# interfacez_main_r2_4.net
KiCad netlist of a schematic drawn in EAGLE
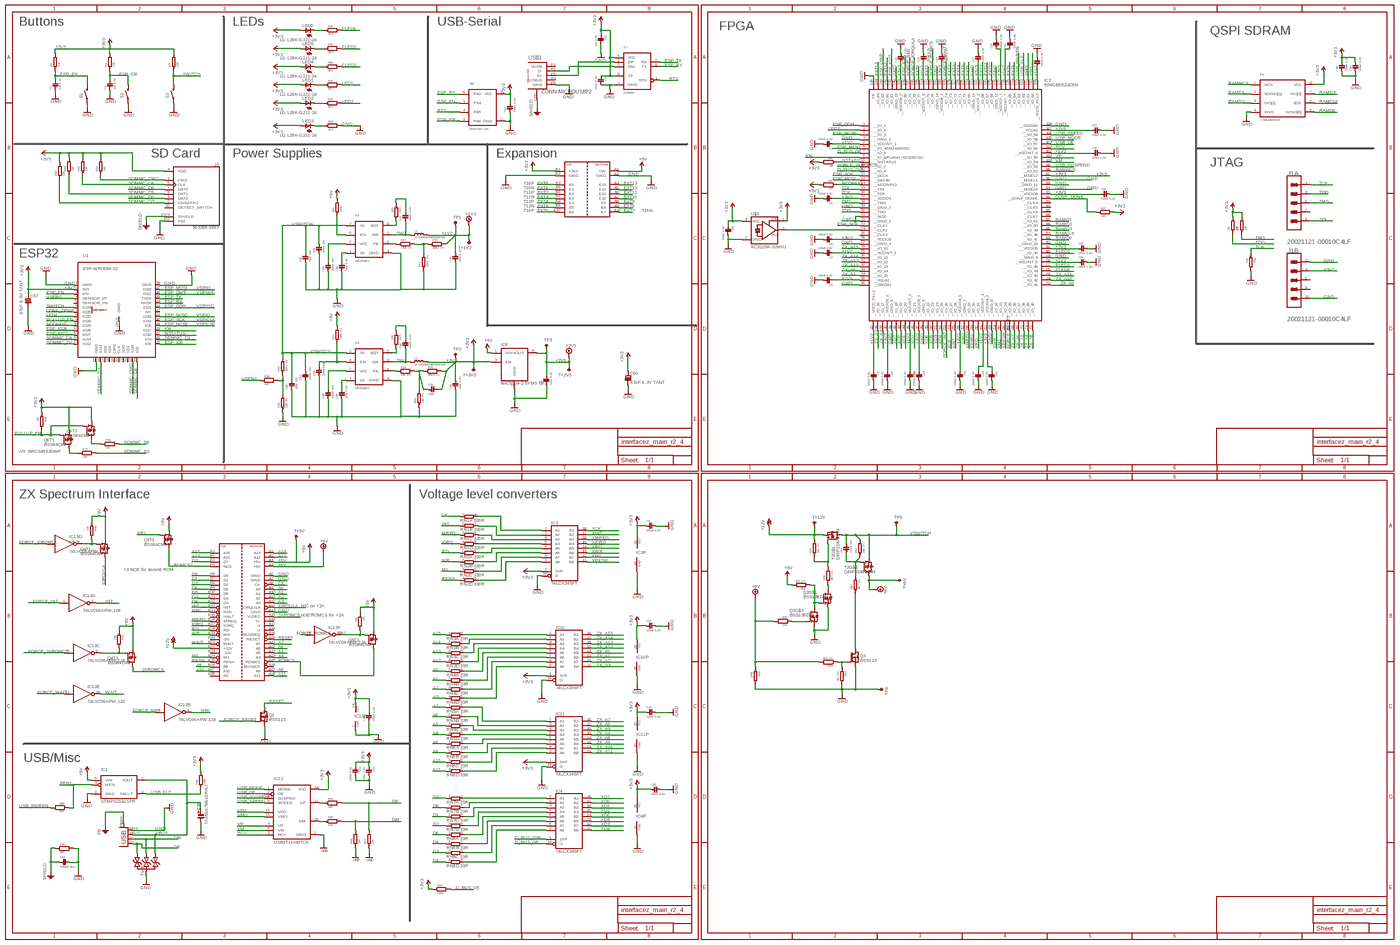
[diagram p0: schematic, sheet 1, overview]
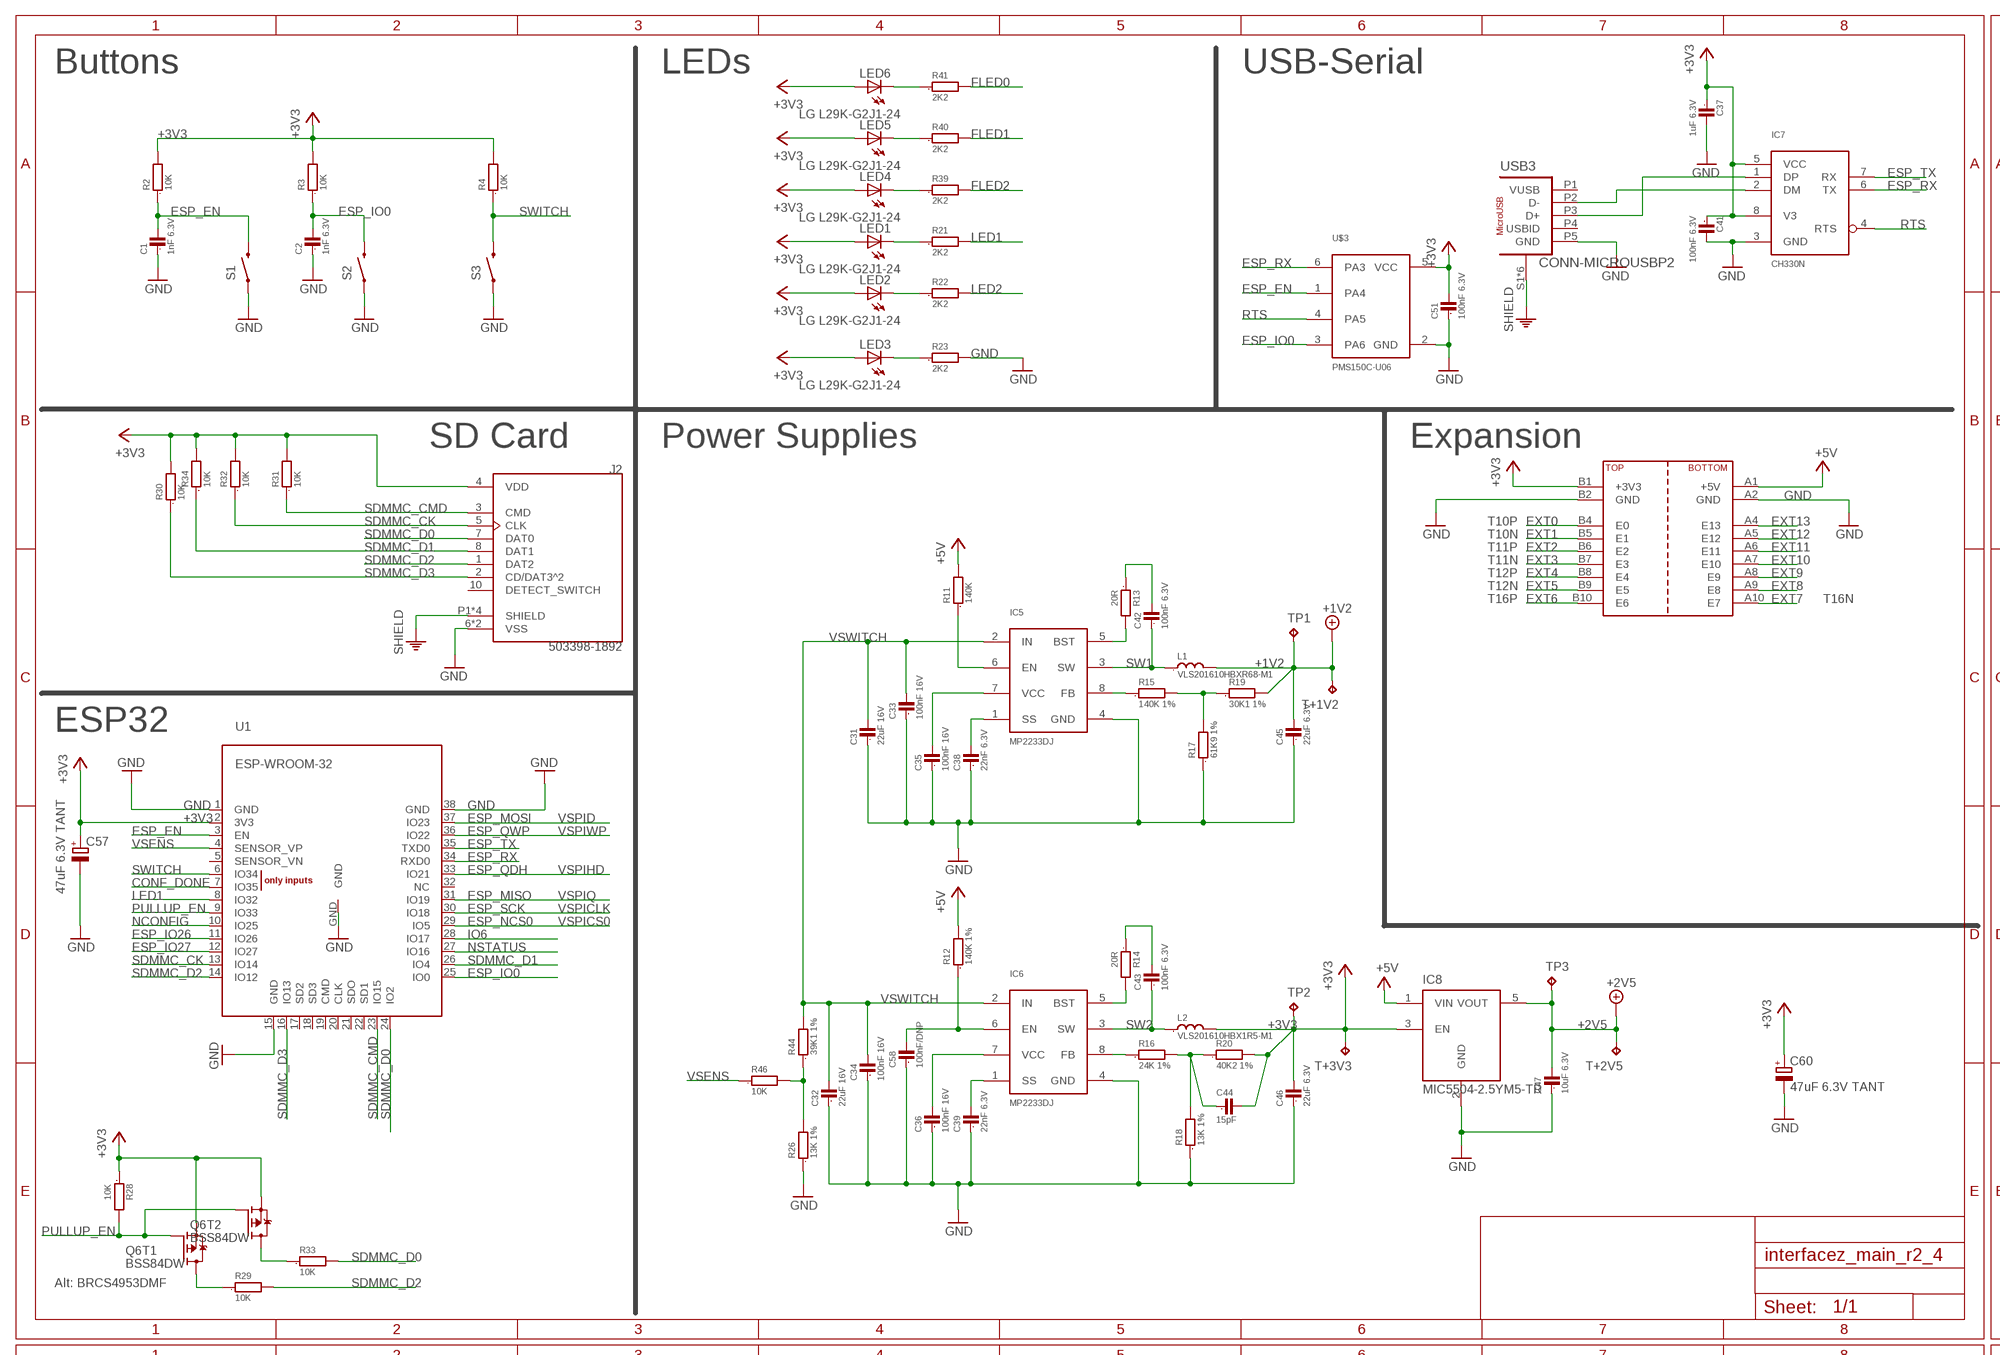
[diagram p1: schematic, sheet 1, part 1 of 4]
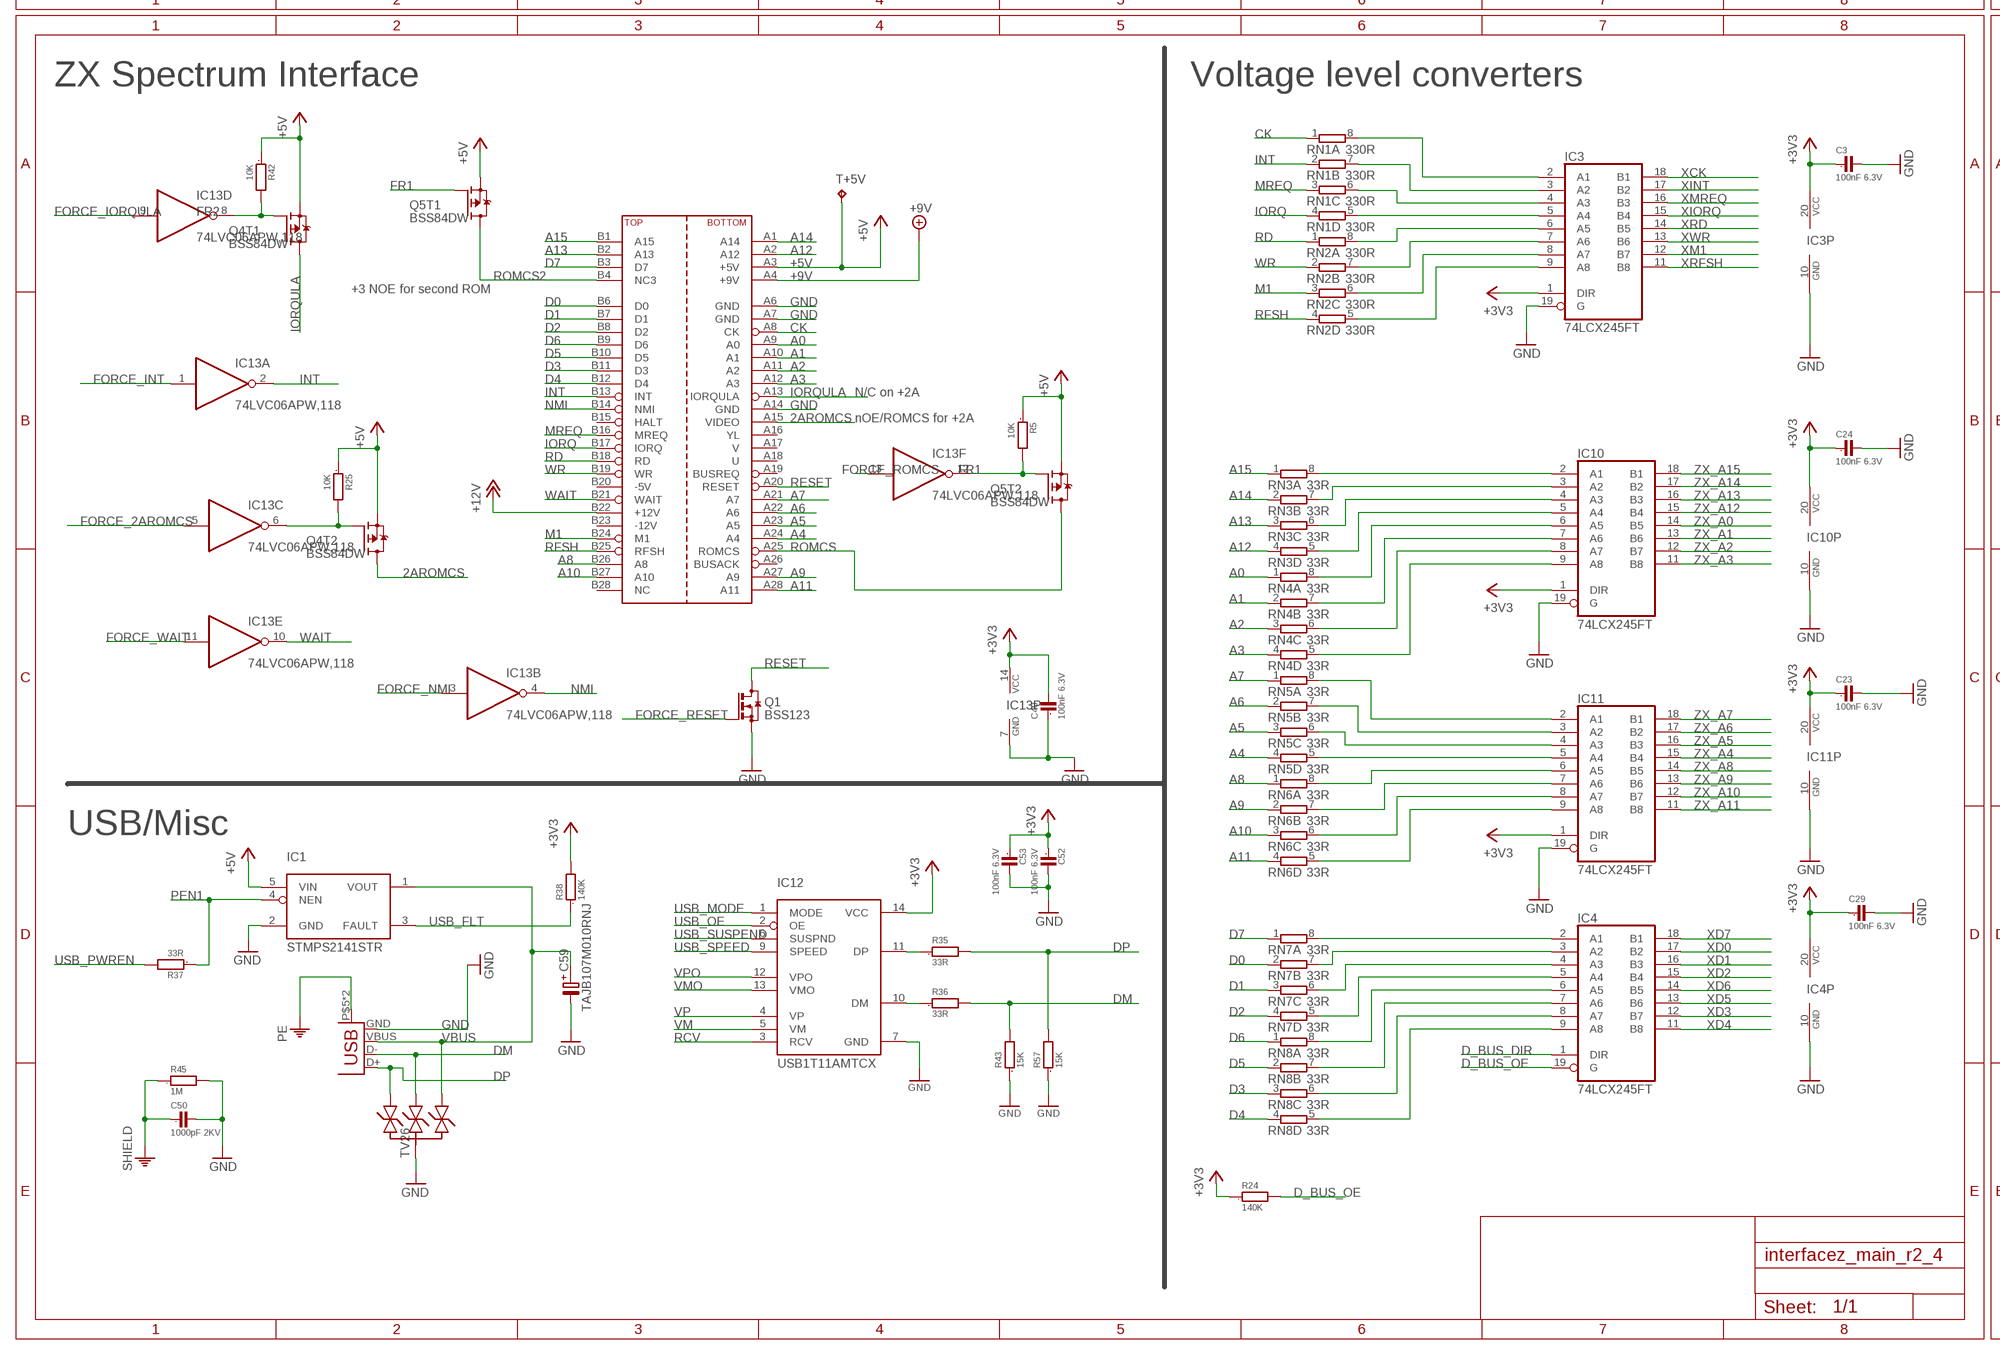
[diagram p2: schematic, sheet 1, part 2 of 4]
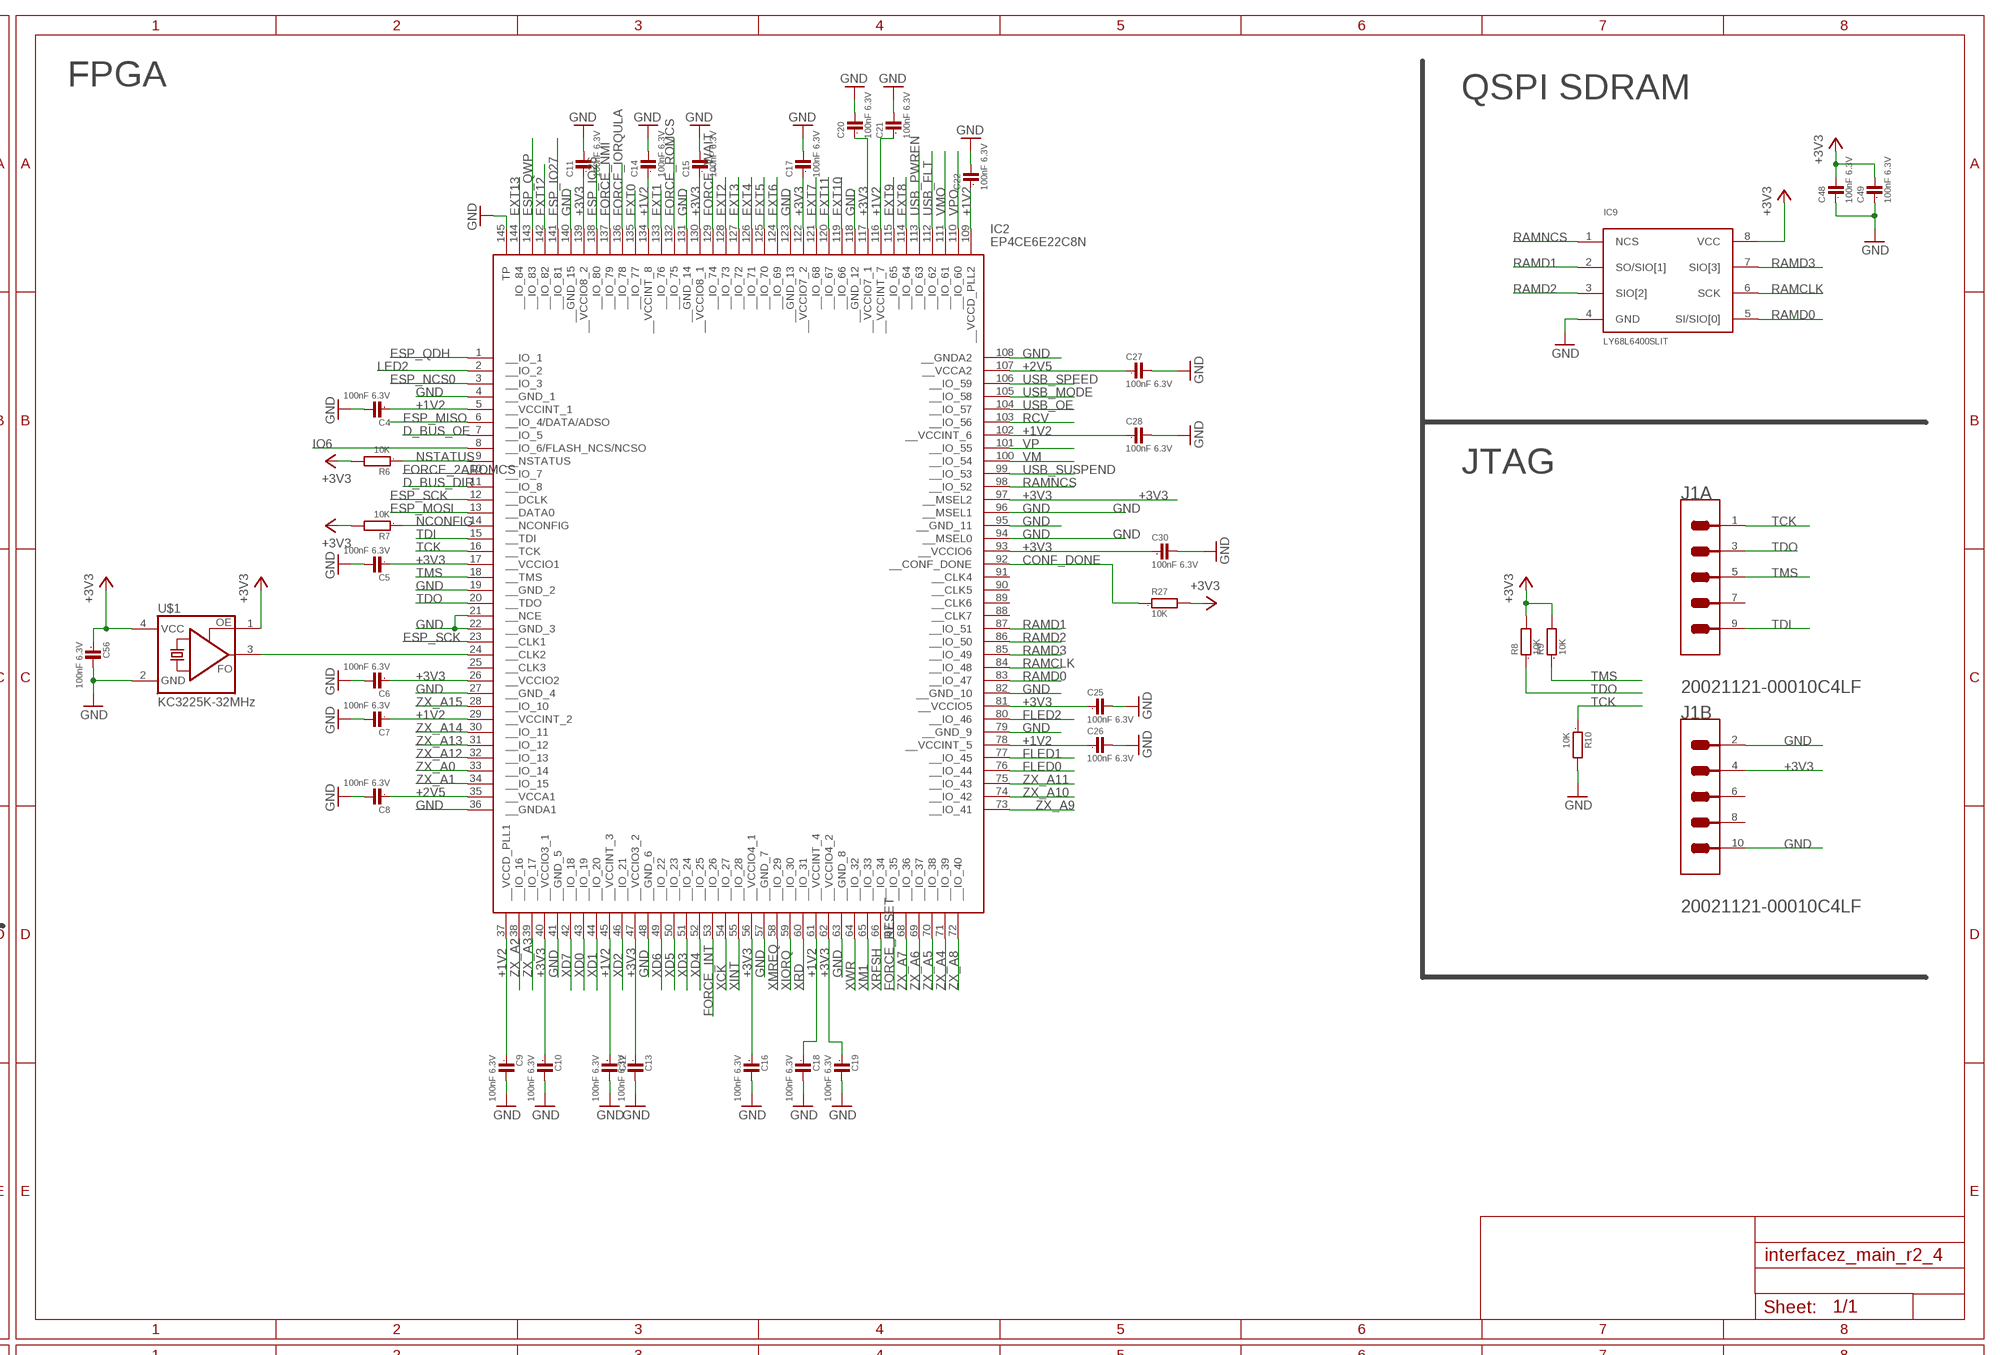
[diagram p3: schematic, sheet 1, part 3 of 4]
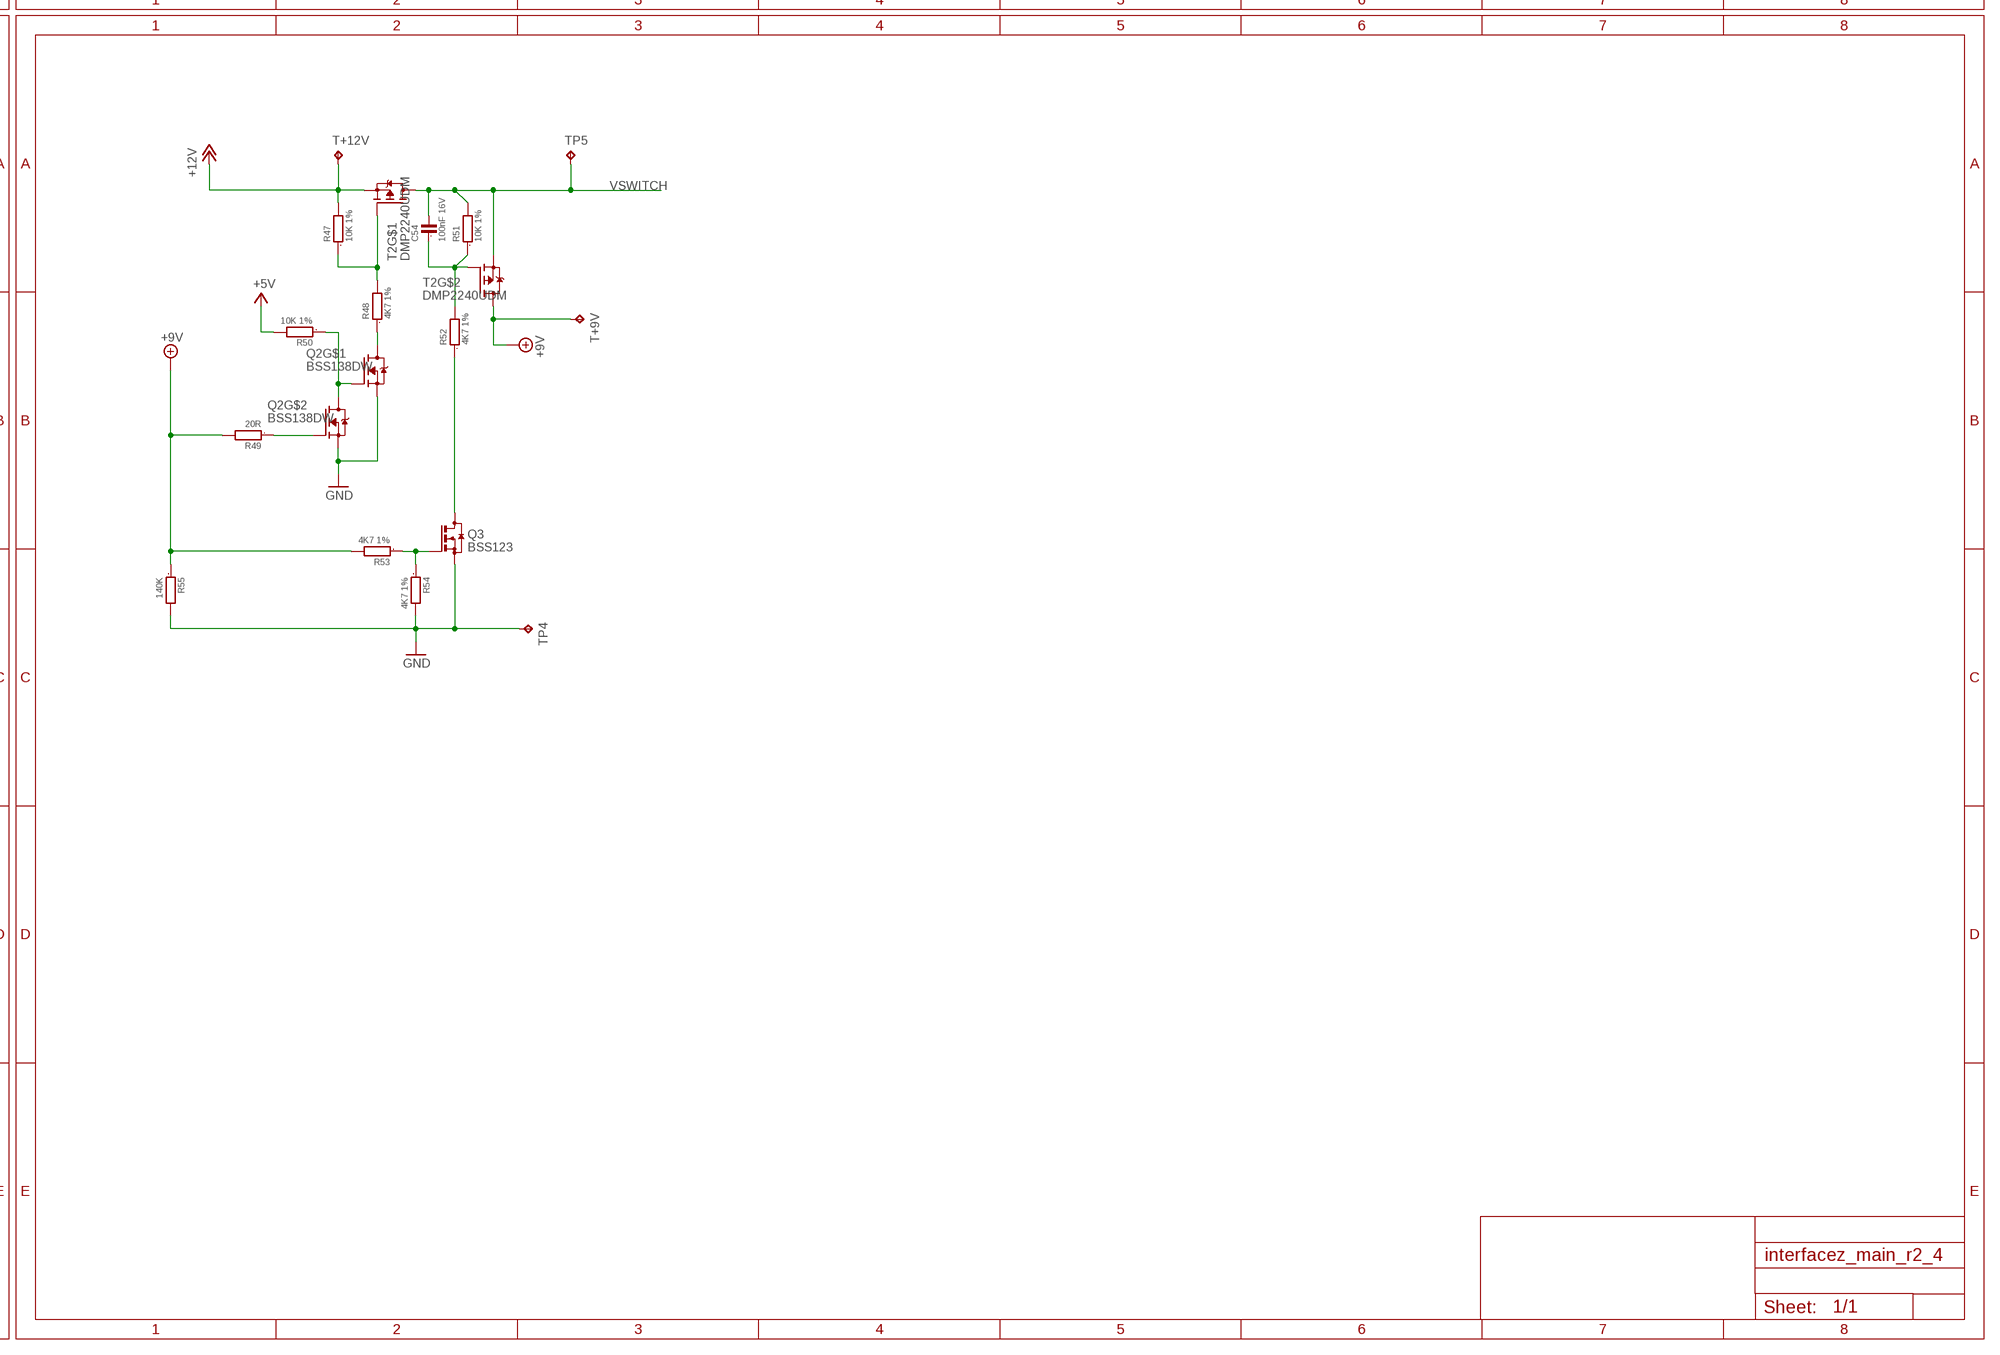
[diagram p4: schematic, sheet 1, part 4 of 4]

(export (version "E")
  (design (tool "Eeschema 10.0.6"))
  (components
    (comp (ref "C1")
      (value "1nF 6.3V")
      (footprint "eagle-import:0603")
      (libsource (lib "eagle-import") (part "C0603"))
    )
    (comp (ref "C2")
      (value "1nF 6.3V")
      (footprint "eagle-import:0603")
      (libsource (lib "eagle-import") (part "C0603"))
    )
    (comp (ref "C3")
      (value "100nF 6.3V")
      (footprint "eagle-import:0603")
      (libsource (lib "eagle-import") (part "C0603"))
    )
    (comp (ref "C4")
      (value "100nF 6.3V")
      (footprint "eagle-import:0603")
      (libsource (lib "eagle-import") (part "C0603"))
    )
    (comp (ref "C5")
      (value "100nF 6.3V")
      (footprint "eagle-import:0603")
      (libsource (lib "eagle-import") (part "C0603"))
    )
    (comp (ref "C6")
      (value "100nF 6.3V")
      (footprint "eagle-import:0603")
      (libsource (lib "eagle-import") (part "C0603"))
    )
    (comp (ref "C7")
      (value "100nF 6.3V")
      (footprint "eagle-import:0603")
      (libsource (lib "eagle-import") (part "C0603"))
    )
    (comp (ref "C8")
      (value "100nF 6.3V")
      (footprint "eagle-import:0603")
      (libsource (lib "eagle-import") (part "C0603"))
    )
    (comp (ref "C9")
      (value "100nF 6.3V")
      (footprint "eagle-import:0603")
      (libsource (lib "eagle-import") (part "C0603"))
    )
    (comp (ref "C10")
      (value "100nF 6.3V")
      (footprint "eagle-import:0603")
      (libsource (lib "eagle-import") (part "C0603"))
    )
    (comp (ref "C11")
      (value "100nF 6.3V")
      (footprint "eagle-import:0603")
      (libsource (lib "eagle-import") (part "C0603"))
    )
    (comp (ref "C12")
      (value "100nF 6.3V")
      (footprint "eagle-import:0603")
      (libsource (lib "eagle-import") (part "C0603"))
    )
    (comp (ref "C13")
      (value "100nF 6.3V")
      (footprint "eagle-import:0603")
      (libsource (lib "eagle-import") (part "C0603"))
    )
    (comp (ref "C14")
      (value "100nF 6.3V")
      (footprint "eagle-import:0603")
      (libsource (lib "eagle-import") (part "C0603"))
    )
    (comp (ref "C15")
      (value "100nF 6.3V")
      (footprint "eagle-import:0603")
      (libsource (lib "eagle-import") (part "C0603"))
    )
    (comp (ref "C16")
      (value "100nF 6.3V")
      (footprint "eagle-import:0603")
      (libsource (lib "eagle-import") (part "C0603"))
    )
    (comp (ref "C17")
      (value "100nF 6.3V")
      (footprint "eagle-import:0603")
      (libsource (lib "eagle-import") (part "C0603"))
    )
    (comp (ref "C18")
      (value "100nF 6.3V")
      (footprint "eagle-import:0603")
      (libsource (lib "eagle-import") (part "C0603"))
    )
    (comp (ref "C19")
      (value "100nF 6.3V")
      (footprint "eagle-import:0603")
      (libsource (lib "eagle-import") (part "C0603"))
    )
    (comp (ref "C20")
      (value "100nF 6.3V")
      (footprint "eagle-import:0603")
      (libsource (lib "eagle-import") (part "C0603"))
    )
    (comp (ref "C21")
      (value "100nF 6.3V")
      (footprint "eagle-import:0603")
      (libsource (lib "eagle-import") (part "C0603"))
    )
    (comp (ref "C22")
      (value "100nF 6.3V")
      (footprint "eagle-import:0603")
      (libsource (lib "eagle-import") (part "C0603"))
    )
    (comp (ref "C23")
      (value "100nF 6.3V")
      (footprint "eagle-import:0603")
      (libsource (lib "eagle-import") (part "C0603"))
    )
    (comp (ref "C24")
      (value "100nF 6.3V")
      (footprint "eagle-import:0603")
      (libsource (lib "eagle-import") (part "C0603"))
    )
    (comp (ref "C25")
      (value "100nF 6.3V")
      (footprint "eagle-import:0603")
      (libsource (lib "eagle-import") (part "C0603"))
    )
    (comp (ref "C26")
      (value "100nF 6.3V")
      (footprint "eagle-import:0603")
      (libsource (lib "eagle-import") (part "C0603"))
    )
    (comp (ref "C27")
      (value "100nF 6.3V")
      (footprint "eagle-import:0603")
      (libsource (lib "eagle-import") (part "C0603"))
    )
    (comp (ref "C28")
      (value "100nF 6.3V")
      (footprint "eagle-import:0603")
      (libsource (lib "eagle-import") (part "C0603"))
    )
    (comp (ref "C29")
      (value "100nF 6.3V")
      (footprint "eagle-import:0603")
      (libsource (lib "eagle-import") (part "C0603"))
    )
    (comp (ref "C30")
      (value "100nF 6.3V")
      (footprint "eagle-import:0603")
      (libsource (lib "eagle-import") (part "C0603"))
    )
    (comp (ref "C31")
      (value "22uF 16V")
      (footprint "eagle-import:1210")
      (libsource (lib "eagle-import") (part "C1210"))
    )
    (comp (ref "C32")
      (value "22uF 16V")
      (footprint "eagle-import:1210")
      (libsource (lib "eagle-import") (part "C1210"))
    )
    (comp (ref "C33")
      (value "100nF 16V")
      (footprint "eagle-import:0603")
      (libsource (lib "eagle-import") (part "C0603"))
    )
    (comp (ref "C34")
      (value "100nF 16V")
      (footprint "eagle-import:0603")
      (libsource (lib "eagle-import") (part "C0603"))
    )
    (comp (ref "C35")
      (value "100nF 16V")
      (footprint "eagle-import:0603")
      (libsource (lib "eagle-import") (part "C0603"))
    )
    (comp (ref "C36")
      (value "100nF 16V")
      (footprint "eagle-import:0603")
      (libsource (lib "eagle-import") (part "C0603"))
    )
    (comp (ref "C37")
      (value "1uF 6.3V")
      (footprint "eagle-import:0603")
      (libsource (lib "eagle-import") (part "C0603"))
    )
    (comp (ref "C38")
      (value "22nF 6.3V")
      (footprint "eagle-import:0603")
      (libsource (lib "eagle-import") (part "C0603"))
    )
    (comp (ref "C39")
      (value "22nF 6.3V")
      (footprint "eagle-import:0603")
      (libsource (lib "eagle-import") (part "C0603"))
    )
    (comp (ref "C40")
      (value "100nF 6.3V")
      (footprint "eagle-import:0603")
      (libsource (lib "eagle-import") (part "C0603"))
    )
    (comp (ref "C41")
      (value "100nF 6.3V")
      (footprint "eagle-import:0603")
      (libsource (lib "eagle-import") (part "C0603"))
    )
    (comp (ref "C42")
      (value "100nF 6.3V")
      (footprint "eagle-import:0603")
      (libsource (lib "eagle-import") (part "C0603"))
    )
    (comp (ref "C43")
      (value "100nF 6.3V")
      (footprint "eagle-import:0603")
      (libsource (lib "eagle-import") (part "C0603"))
    )
    (comp (ref "C44")
      (value "15pF")
      (footprint "eagle-import:0603")
      (libsource (lib "eagle-import") (part "C0603"))
    )
    (comp (ref "C45")
      (value "22uF 6.3V")
      (footprint "eagle-import:0805")
      (libsource (lib "eagle-import") (part "C0805"))
    )
    (comp (ref "C46")
      (value "22uF 6.3V")
      (footprint "eagle-import:0805")
      (libsource (lib "eagle-import") (part "C0805"))
    )
    (comp (ref "C47")
      (value "10uF 6.3V")
      (footprint "eagle-import:0805")
      (libsource (lib "eagle-import") (part "C0805"))
    )
    (comp (ref "C48")
      (value "100nF 6.3V")
      (footprint "eagle-import:0603")
      (libsource (lib "eagle-import") (part "C0603"))
    )
    (comp (ref "C49")
      (value "100nF 6.3V")
      (footprint "eagle-import:0603")
      (libsource (lib "eagle-import") (part "C0603"))
    )
    (comp (ref "C50")
      (value "1000pF 2KV")
      (footprint "eagle-import:1210")
      (libsource (lib "eagle-import") (part "C1210"))
    )
    (comp (ref "C51")
      (value "100nF 6.3V")
      (footprint "eagle-import:0603")
      (libsource (lib "eagle-import") (part "C0603"))
    )
    (comp (ref "C52")
      (value "100nF 6.3V")
      (footprint "eagle-import:0603")
      (libsource (lib "eagle-import") (part "C0603"))
    )
    (comp (ref "C53")
      (value "100nF 6.3V")
      (footprint "eagle-import:0603")
      (libsource (lib "eagle-import") (part "C0603"))
    )
    (comp (ref "C54")
      (value "100nF 16V")
      (footprint "eagle-import:0603")
      (libsource (lib "eagle-import") (part "C0603"))
    )
    (comp (ref "C56")
      (value "100nF 6.3V")
      (footprint "eagle-import:0603")
      (libsource (lib "eagle-import") (part "C0603"))
    )
    (comp (ref "C57")
      (value "47uF 6.3V TANT")
      (footprint "eagle-import:TANT_CASE_A")
      (libsource (lib "eagle-import") (part "TANT_CASE_A"))
    )
    (comp (ref "C58")
      (value "100nF/DNP")
      (footprint "eagle-import:0603")
      (libsource (lib "eagle-import") (part "C0603"))
    )
    (comp (ref "C59")
      (value "TAJB107M010RNJ")
      (footprint "eagle-import:TE-B-3528")
      (libsource (lib "eagle-import") (part "C-PR-SMD-TE-B"))
    )
    (comp (ref "C60")
      (value "47uF 6.3V TANT")
      (footprint "eagle-import:TANT_CASE_A")
      (libsource (lib "eagle-import") (part "TANT_CASE_A"))
    )
    (comp (ref "CONN1")
      (value "ZX_EDGE_DAUGHTERBOARD")
      (footprint "eagle-import:ZX-EDGE-DAUGHTERBOARD")
      (libsource (lib "eagle-import") (part "ZX_EDGE_DAUGHTERBOARD"))
    )
    (comp (ref "IC1")
      (value "STMPS2141STR")
      (footprint "eagle-import:SOT23-5L")
      (libsource (lib "eagle-import") (part "STMPS2141STR"))
    )
    (comp (ref "IC2")
      (value "EP4CE6E22C8N")
      (footprint "eagle-import:QFP50P2200X2200X165-145N")
      (fields (field (name "MOUSER_PART_NUMBER") "989-EP4CE6E22C8N"))
      (libsource (lib "eagle-import") (part "EP4CE6E22C8N"))
    )
    (comp (ref "IC3")
      (value "74LCX245FT")
      (footprint "eagle-import:TSSOP20")
      (libsource (lib "eagle-import") (part "74245"))
    )
    (comp (ref "IC4")
      (value "74LCX245FT")
      (footprint "eagle-import:TSSOP20")
      (libsource (lib "eagle-import") (part "74245"))
    )
    (comp (ref "IC5")
      (value "MP2233DJ")
      (footprint "eagle-import:SOT23-8L")
      (libsource (lib "eagle-import") (part "MP2233DJ"))
    )
    (comp (ref "IC6")
      (value "MP2233DJ")
      (footprint "eagle-import:SOT23-8L")
      (libsource (lib "eagle-import") (part "MP2233DJ"))
    )
    (comp (ref "IC7")
      (value "CH330N")
      (footprint "eagle-import:SOIC8")
      (libsource (lib "eagle-import") (part "CH330N"))
    )
    (comp (ref "IC8")
      (value "MIC5504-2.5YM5-TR")
      (footprint "eagle-import:SOT23-5L")
      (libsource (lib "eagle-import") (part "MIC550X"))
    )
    (comp (ref "IC9")
      (value "LY68L6400SLIT")
      (footprint "eagle-import:SOIC8")
      (libsource (lib "eagle-import") (part "LY68L6400SLIT"))
    )
    (comp (ref "IC10")
      (value "74LCX245FT")
      (footprint "eagle-import:TSSOP20")
      (libsource (lib "eagle-import") (part "74245"))
    )
    (comp (ref "IC11")
      (value "74LCX245FT")
      (footprint "eagle-import:TSSOP20")
      (libsource (lib "eagle-import") (part "74245"))
    )
    (comp (ref "IC12")
      (value "USB1T11AMTCX")
      (footprint "eagle-import:TSSOP14")
      (libsource (lib "eagle-import") (part "USB1TMTCX11A"))
    )
    (comp (ref "IC13")
      (value "74LVC06APW,118")
      (footprint "eagle-import:TSSOP14")
      (libsource (lib "eagle-import") (part "7406APW,118LVC"))
    )
    (comp (ref "J1")
      (value "AMPHENOL_ICC_-_FCI_20021121-00010C4LFAMPHENOL_ICC_-_FCI_20021121-00010C4LF_0_0")
      (footprint "eagle-import:AMPHENOL_ICC_-_FCI_20021121-00010C4LF_0")
      (fields
        (field (name "DIGIKEY_PART_NUMBER") "609-3695-1-ND")
        (field (name "MF") "Amphenol ICC / FCI")
        (field (name "MOUSER_PART_NUMBER") "649-202112100010C4LF")
      )
      (libsource (lib "eagle-import") (part "AMPHENOL_ICC_-_FCI_20021121-00010C4LFAMPHENOL_ICC_-_FCI_20021121-00010C4LF_0_0"))
    )
    (comp (ref "J2")
      (value "503398-1892")
      (footprint "eagle-import:MOLEX_503398-1892")
      (fields (field (name "MF") "Molex"))
      (libsource (lib "eagle-import") (part "503398-1892"))
    )
    (comp (ref "L1")
      (value "VLS201610HBXR68-M1")
      (footprint "eagle-import:IND_0806")
      (libsource (lib "eagle-import") (part "VLS201610HBXR68-M1"))
    )
    (comp (ref "L2")
      (value "VLS201610HBX1R5-M1")
      (footprint "eagle-import:IND_0806")
      (libsource (lib "eagle-import") (part "VLS201610HBX1R5-M1"))
    )
    (comp (ref "LED1")
      (value "LG L29K-G2J1-24")
      (footprint "eagle-import:LED-603")
      (libsource (lib "eagle-import") (part "LED-0603"))
    )
    (comp (ref "LED2")
      (value "LG L29K-G2J1-24")
      (footprint "eagle-import:LED-603")
      (libsource (lib "eagle-import") (part "LED-0603"))
    )
    (comp (ref "LED3")
      (value "LG L29K-G2J1-24")
      (footprint "eagle-import:LED-603")
      (libsource (lib "eagle-import") (part "LED-0603"))
    )
    (comp (ref "LED4")
      (value "LG L29K-G2J1-24")
      (footprint "eagle-import:LED-603")
      (libsource (lib "eagle-import") (part "LED-0603"))
    )
    (comp (ref "LED5")
      (value "LG L29K-G2J1-24")
      (footprint "eagle-import:LED-603")
      (libsource (lib "eagle-import") (part "LED-0603"))
    )
    (comp (ref "LED6")
      (value "LG L29K-G2J1-24")
      (footprint "eagle-import:LED-603")
      (libsource (lib "eagle-import") (part "LED-0603"))
    )
    (comp (ref "Q1")
      (value "BSS123")
      (footprint "eagle-import:SOT23")
      (libsource (lib "eagle-import") (part "BSS123"))
    )
    (comp (ref "Q2")
      (value "BSS138DW")
      (footprint "eagle-import:SOT363_INFINEON")
      (libsource (lib "eagle-import") (part "BSS138DW"))
    )
    (comp (ref "Q3")
      (value "BSS123")
      (footprint "eagle-import:SOT23")
      (libsource (lib "eagle-import") (part "BSS123"))
    )
    (comp (ref "Q4")
      (value "BSS84DW")
      (footprint "eagle-import:SOT363_INFINEON")
      (libsource (lib "eagle-import") (part "BSS84DW"))
    )
    (comp (ref "Q5")
      (value "BSS84DW")
      (footprint "eagle-import:SOT363_INFINEON")
      (libsource (lib "eagle-import") (part "BSS84DW"))
    )
    (comp (ref "Q6")
      (value "BSS84DW")
      (footprint "eagle-import:SOT363_INFINEON")
      (libsource (lib "eagle-import") (part "BSS84DW"))
    )
    (comp (ref "R2")
      (value "10K")
      (footprint "eagle-import:0603")
      (libsource (lib "eagle-import") (part "R0603"))
    )
    (comp (ref "R3")
      (value "10K")
      (footprint "eagle-import:0603")
      (libsource (lib "eagle-import") (part "R0603"))
    )
    (comp (ref "R4")
      (value "10K")
      (footprint "eagle-import:0603")
      (libsource (lib "eagle-import") (part "R0603"))
    )
    (comp (ref "R5")
      (value "10K")
      (footprint "eagle-import:0603")
      (libsource (lib "eagle-import") (part "R0603"))
    )
    (comp (ref "R6")
      (value "10K")
      (footprint "eagle-import:0603")
      (libsource (lib "eagle-import") (part "R0603"))
    )
    (comp (ref "R7")
      (value "10K")
      (footprint "eagle-import:0603")
      (libsource (lib "eagle-import") (part "R0603"))
    )
    (comp (ref "R8")
      (value "10K")
      (footprint "eagle-import:0603")
      (libsource (lib "eagle-import") (part "R0603"))
    )
    (comp (ref "R9")
      (value "10K")
      (footprint "eagle-import:0603")
      (libsource (lib "eagle-import") (part "R0603"))
    )
    (comp (ref "R10")
      (value "10K")
      (footprint "eagle-import:0603")
      (libsource (lib "eagle-import") (part "R0603"))
    )
    (comp (ref "R11")
      (value "140K")
      (footprint "eagle-import:0603")
      (libsource (lib "eagle-import") (part "R0603"))
    )
    (comp (ref "R12")
      (value "140K 1%")
      (footprint "eagle-import:0603")
      (libsource (lib "eagle-import") (part "R0603"))
    )
    (comp (ref "R13")
      (value "20R")
      (footprint "eagle-import:0603")
      (libsource (lib "eagle-import") (part "R0603"))
    )
    (comp (ref "R14")
      (value "20R")
      (footprint "eagle-import:0603")
      (libsource (lib "eagle-import") (part "R0603"))
    )
    (comp (ref "R15")
      (value "140K 1%")
      (footprint "eagle-import:0603")
      (libsource (lib "eagle-import") (part "R0603"))
    )
    (comp (ref "R16")
      (value "24K 1%")
      (footprint "eagle-import:0603")
      (libsource (lib "eagle-import") (part "R0603"))
    )
    (comp (ref "R17")
      (value "61K9 1%")
      (footprint "eagle-import:0603")
      (libsource (lib "eagle-import") (part "R0603"))
    )
    (comp (ref "R18")
      (value "13K 1%")
      (footprint "eagle-import:0603")
      (libsource (lib "eagle-import") (part "R0603"))
    )
    (comp (ref "R19")
      (value "30K1 1%")
      (footprint "eagle-import:0603")
      (libsource (lib "eagle-import") (part "R0603"))
    )
    (comp (ref "R20")
      (value "40K2 1%")
      (footprint "eagle-import:0603")
      (libsource (lib "eagle-import") (part "R0603"))
    )
    (comp (ref "R21")
      (value "2K2")
      (footprint "eagle-import:0603")
      (libsource (lib "eagle-import") (part "R0603"))
    )
    (comp (ref "R22")
      (value "2K2")
      (footprint "eagle-import:0603")
      (libsource (lib "eagle-import") (part "R0603"))
    )
    (comp (ref "R23")
      (value "2K2")
      (footprint "eagle-import:0603")
      (libsource (lib "eagle-import") (part "R0603"))
    )
    (comp (ref "R24")
      (value "140K")
      (footprint "eagle-import:0603")
      (libsource (lib "eagle-import") (part "R0603"))
    )
    (comp (ref "R25")
      (value "10K")
      (footprint "eagle-import:0603")
      (libsource (lib "eagle-import") (part "R0603"))
    )
    (comp (ref "R26")
      (value "13K 1%")
      (footprint "eagle-import:0603")
      (libsource (lib "eagle-import") (part "R0603"))
    )
    (comp (ref "R27")
      (value "10K")
      (footprint "eagle-import:0603")
      (libsource (lib "eagle-import") (part "R0603"))
    )
    (comp (ref "R28")
      (value "10K")
      (footprint "eagle-import:0603")
      (libsource (lib "eagle-import") (part "R0603"))
    )
    (comp (ref "R29")
      (value "10K")
      (footprint "eagle-import:0603")
      (libsource (lib "eagle-import") (part "R0603"))
    )
    (comp (ref "R30")
      (value "10K")
      (footprint "eagle-import:0603")
      (libsource (lib "eagle-import") (part "R0603"))
    )
    (comp (ref "R31")
      (value "10K")
      (footprint "eagle-import:0603")
      (libsource (lib "eagle-import") (part "R0603"))
    )
    (comp (ref "R32")
      (value "10K")
      (footprint "eagle-import:0603")
      (libsource (lib "eagle-import") (part "R0603"))
    )
    (comp (ref "R33")
      (value "10K")
      (footprint "eagle-import:0603")
      (libsource (lib "eagle-import") (part "R0603"))
    )
    (comp (ref "R34")
      (value "10K")
      (footprint "eagle-import:0603")
      (libsource (lib "eagle-import") (part "R0603"))
    )
    (comp (ref "R35")
      (value "33R")
      (footprint "eagle-import:0603")
      (libsource (lib "eagle-import") (part "R0603"))
    )
    (comp (ref "R36")
      (value "33R")
      (footprint "eagle-import:0603")
      (libsource (lib "eagle-import") (part "R0603"))
    )
    (comp (ref "R37")
      (value "33R")
      (footprint "eagle-import:0603")
      (libsource (lib "eagle-import") (part "R0603"))
    )
    (comp (ref "R38")
      (value "140K")
      (footprint "eagle-import:0603")
      (libsource (lib "eagle-import") (part "R0603"))
    )
    (comp (ref "R39")
      (value "2K2")
      (footprint "eagle-import:0603")
      (libsource (lib "eagle-import") (part "R0603"))
    )
    (comp (ref "R40")
      (value "2K2")
      (footprint "eagle-import:0603")
      (libsource (lib "eagle-import") (part "R0603"))
    )
    (comp (ref "R41")
      (value "2K2")
      (footprint "eagle-import:0603")
      (libsource (lib "eagle-import") (part "R0603"))
    )
    (comp (ref "R42")
      (value "10K")
      (footprint "eagle-import:0603")
      (libsource (lib "eagle-import") (part "R0603"))
    )
    (comp (ref "R43")
      (value "15K")
      (footprint "eagle-import:0603")
      (libsource (lib "eagle-import") (part "R0603"))
    )
    (comp (ref "R44")
      (value "39K1 1%")
      (footprint "eagle-import:0603")
      (libsource (lib "eagle-import") (part "R0603"))
    )
    (comp (ref "R45")
      (value "1M")
      (footprint "eagle-import:0805")
      (libsource (lib "eagle-import") (part "R0805"))
    )
    (comp (ref "R46")
      (value "10K")
      (footprint "eagle-import:0603")
      (libsource (lib "eagle-import") (part "R0603"))
    )
    (comp (ref "R47")
      (value "10K 1%")
      (footprint "eagle-import:0603")
      (libsource (lib "eagle-import") (part "R0603"))
    )
    (comp (ref "R48")
      (value "4K7 1%")
      (footprint "eagle-import:0603")
      (libsource (lib "eagle-import") (part "R0603"))
    )
    (comp (ref "R49")
      (value "20R")
      (footprint "eagle-import:0603")
      (libsource (lib "eagle-import") (part "R0603"))
    )
    (comp (ref "R50")
      (value "10K 1%")
      (footprint "eagle-import:0603")
      (libsource (lib "eagle-import") (part "R0603"))
    )
    (comp (ref "R51")
      (value "10K 1%")
      (footprint "eagle-import:0603")
      (libsource (lib "eagle-import") (part "R0603"))
    )
    (comp (ref "R52")
      (value "4K7 1%")
      (footprint "eagle-import:0603")
      (libsource (lib "eagle-import") (part "R0603"))
    )
    (comp (ref "R53")
      (value "4K7 1%")
      (footprint "eagle-import:0603")
      (libsource (lib "eagle-import") (part "R0603"))
    )
    (comp (ref "R54")
      (value "4K7 1%")
      (footprint "eagle-import:0603")
      (libsource (lib "eagle-import") (part "R0603"))
    )
    (comp (ref "R55")
      (value "140K")
      (footprint "eagle-import:0603")
      (libsource (lib "eagle-import") (part "R0603"))
    )
    (comp (ref "R57")
      (value "15K")
      (footprint "eagle-import:0603")
      (libsource (lib "eagle-import") (part "R0603"))
    )
    (comp (ref "RN1")
      (value "330R")
      (footprint "eagle-import:EXB28V")
      (libsource (lib "eagle-import") (part "4R-NEXB28V"))
    )
    (comp (ref "RN2")
      (value "330R")
      (footprint "eagle-import:EXB28V")
      (libsource (lib "eagle-import") (part "4R-NEXB28V"))
    )
    (comp (ref "RN3")
      (value "33R")
      (footprint "eagle-import:EXB28V")
      (libsource (lib "eagle-import") (part "4R-NEXB28V"))
    )
    (comp (ref "RN4")
      (value "33R")
      (footprint "eagle-import:EXB28V")
      (libsource (lib "eagle-import") (part "4R-NEXB28V"))
    )
    (comp (ref "RN5")
      (value "33R")
      (footprint "eagle-import:EXB28V")
      (libsource (lib "eagle-import") (part "4R-NEXB28V"))
    )
    (comp (ref "RN6")
      (value "33R")
      (footprint "eagle-import:EXB28V")
      (libsource (lib "eagle-import") (part "4R-NEXB28V"))
    )
    (comp (ref "RN7")
      (value "33R")
      (footprint "eagle-import:EXB28V")
      (libsource (lib "eagle-import") (part "4R-NEXB28V"))
    )
    (comp (ref "RN8")
      (value "33R")
      (footprint "eagle-import:EXB28V")
      (libsource (lib "eagle-import") (part "4R-NEXB28V"))
    )
    (comp (ref "S1")
      (value "SWITCHES_SMD-4")
      (footprint "eagle-import:TACTILE_SWITCH_TALL")
      (libsource (lib "eagle-import") (part "SWITCHES_SMD-4"))
    )
    (comp (ref "S2")
      (value "SWITCHES_SMD-4")
      (footprint "eagle-import:TACTILE_SWITCH_TALL")
      (libsource (lib "eagle-import") (part "SWITCHES_SMD-4"))
    )
    (comp (ref "S3")
      (value "SWITCHES_SMD-4")
      (footprint "eagle-import:TACTILE_SWITCH_TALL")
      (libsource (lib "eagle-import") (part "SWITCHES_SMD-4"))
    )
    (comp (ref "T+1V2")
      (value "TPTP12SQ")
      (footprint "eagle-import:TP12SQ")
      (libsource (lib "eagle-import") (part "TPTP12SQ"))
    )
    (comp (ref "T+2V5")
      (value "TPTP12SQ")
      (footprint "eagle-import:TP12SQ")
      (libsource (lib "eagle-import") (part "TPTP12SQ"))
    )
    (comp (ref "T+3V3")
      (value "TPTP12SQ")
      (footprint "eagle-import:TP12SQ")
      (libsource (lib "eagle-import") (part "TPTP12SQ"))
    )
    (comp (ref "T+5V")
      (value "TPTP12SQ")
      (footprint "eagle-import:TP12SQ")
      (libsource (lib "eagle-import") (part "TPTP12SQ"))
    )
    (comp (ref "T+9V")
      (value "TPTP12SQ")
      (footprint "eagle-import:TP12SQ")
      (libsource (lib "eagle-import") (part "TPTP12SQ"))
    )
    (comp (ref "T+12V")
      (value "TPTP12SQ")
      (footprint "eagle-import:TP12SQ")
      (libsource (lib "eagle-import") (part "TPTP12SQ"))
    )
    (comp (ref "T2")
      (value "DMP2240UDM")
      (footprint "eagle-import:SOT23-6")
      (libsource (lib "eagle-import") (part "MOSFET-P-DUAL-SOT23-6"))
    )
    (comp (ref "TP1")
      (value "TPTP12R")
      (footprint "eagle-import:TP12R")
      (libsource (lib "eagle-import") (part "TPTP12R"))
    )
    (comp (ref "TP2")
      (value "TPTP12R")
      (footprint "eagle-import:TP12R")
      (libsource (lib "eagle-import") (part "TPTP12R"))
    )
    (comp (ref "TP3")
      (value "TPTP12R")
      (footprint "eagle-import:TP12R")
      (libsource (lib "eagle-import") (part "TPTP12R"))
    )
    (comp (ref "TP4")
      (value "TPPAD1-13")
      (footprint "eagle-import:P1-13")
      (libsource (lib "eagle-import") (part "TPPAD1-13"))
    )
    (comp (ref "TP5")
      (value "TPTP12SQ")
      (footprint "eagle-import:TP12SQ")
      (libsource (lib "eagle-import") (part "TPTP12SQ"))
    )
    (comp (ref "TV26")
      (value "SP0503BAHT")
      (footprint "eagle-import:SP0503")
      (libsource (lib "eagle-import") (part "SP0503BAHT"))
    )
    (comp (ref "U$1")
      (value "KC3225K-32MHz")
      (footprint "eagle-import:KC3225K")
      (libsource (lib "eagle-import") (part "KC3225K"))
    )
    (comp (ref "U$3")
      (value "PMS150C-U06")
      (footprint "eagle-import:SOT23-6")
      (libsource (lib "eagle-import") (part "PMS150C-U06"))
    )
    (comp (ref "U$5")
      (value "INTERFACEZ_EDGEDAUGHTER")
      (footprint "eagle-import:INTERFACEZ_EXPANSION_DAUGHTERCARD")
      (libsource (lib "eagle-import") (part "INTERFACEZ_EDGEDAUGHTER"))
    )
    (comp (ref "U1")
      (value "ESP-WROOM-32")
      (footprint "eagle-import:ESP-WROOM-32")
      (libsource (lib "eagle-import") (part "ESP-WROOM-32"))
    )
    (comp (ref "USB2")
      (value "USB-A-H")
      (footprint "eagle-import:USB-A-H")
      (libsource (lib "eagle-import") (part "USB-A-H"))
    )
    (comp (ref "USB3")
      (value "CONN-MICROUSBP2")
      (footprint "eagle-import:MICROUSB_SMD_TH_7.5MM_4.85MM")
      (libsource (lib "eagle-import") (part "CONN-MICROUSBP2"))
    )
  )
  (nets
    (net (code "1") (name "+1V2") (class "Default")
      (node (ref "C12") (pin "1") (pinfunction "1_1") (pintype "passive"))
      (node (ref "C14") (pin "1") (pinfunction "1_1") (pintype "passive"))
      (node (ref "C18") (pin "1") (pinfunction "1_1") (pintype "passive"))
      (node (ref "C21") (pin "1") (pinfunction "1_1") (pintype "passive"))
      (node (ref "C22") (pin "1") (pinfunction "1_1") (pintype "passive"))
      (node (ref "C26") (pin "1") (pinfunction "1_1") (pintype "passive"))
      (node (ref "C28") (pin "1") (pinfunction "1_1") (pintype "passive"))
      (node (ref "C4") (pin "1") (pinfunction "1_1") (pintype "passive"))
      (node (ref "C45") (pin "2") (pinfunction "2_2") (pintype "passive"))
      (node (ref "C7") (pin "1") (pinfunction "1_1") (pintype "passive"))
      (node (ref "C9") (pin "1") (pinfunction "1_1") (pintype "passive"))
      (node (ref "IC2") (pin "102") (pinfunction "__VCCINT_6_102") (pintype "power_in"))
      (node (ref "IC2") (pin "109") (pinfunction "__VCCD_PLL2_109") (pintype "power_in"))
      (node (ref "IC2") (pin "116") (pinfunction "__VCCINT_7_116") (pintype "power_in"))
      (node (ref "IC2") (pin "134") (pinfunction "__VCCINT_8_134") (pintype "power_in"))
      (node (ref "IC2") (pin "29") (pinfunction "__VCCINT_2_29") (pintype "power_in"))
      (node (ref "IC2") (pin "37") (pinfunction "__VCCD_PLL1_37") (pintype "power_in"))
      (node (ref "IC2") (pin "45") (pinfunction "__VCCINT_3_45") (pintype "power_in"))
      (node (ref "IC2") (pin "5") (pinfunction "__VCCINT_1_5") (pintype "power_in"))
      (node (ref "IC2") (pin "61") (pinfunction "__VCCINT_4_61") (pintype "power_in"))
      (node (ref "IC2") (pin "78") (pinfunction "__VCCINT_5_78") (pintype "power_in"))
      (node (ref "L1") (pin "P$2") (pinfunction "2_P$2") (pintype "passive"))
      (node (ref "R19") (pin "2") (pinfunction "2_2") (pintype "passive"))
      (node (ref "T+1V2") (pin "TP") (pinfunction "TP_TP") (pintype "input"))
      (node (ref "TP1") (pin "TP") (pinfunction "TP_TP") (pintype "input"))
    )
    (net (code "2") (name "+2V5") (class "Default")
      (node (ref "C27") (pin "1") (pinfunction "1_1") (pintype "passive"))
      (node (ref "C47") (pin "2") (pinfunction "2_2") (pintype "passive"))
      (node (ref "C8") (pin "1") (pinfunction "1_1") (pintype "passive"))
      (node (ref "IC2") (pin "107") (pinfunction "__VCCA2_107") (pintype "power_in"))
      (node (ref "IC2") (pin "35") (pinfunction "__VCCA1_35") (pintype "power_in"))
      (node (ref "IC8") (pin "5") (pinfunction "VOUT_5") (pintype "power_in"))
      (node (ref "T+2V5") (pin "TP") (pinfunction "TP_TP") (pintype "input"))
      (node (ref "TP3") (pin "TP") (pinfunction "TP_TP") (pintype "input"))
    )
    (net (code "3") (name "+3V3") (class "Default")
      (node (ref "C10") (pin "1") (pinfunction "1_1") (pintype "passive"))
      (node (ref "C11") (pin "1") (pinfunction "1_1") (pintype "passive"))
      (node (ref "C13") (pin "1") (pinfunction "1_1") (pintype "passive"))
      (node (ref "C15") (pin "1") (pinfunction "1_1") (pintype "passive"))
      (node (ref "C16") (pin "1") (pinfunction "1_1") (pintype "passive"))
      (node (ref "C17") (pin "1") (pinfunction "1_1") (pintype "passive"))
      (node (ref "C19") (pin "1") (pinfunction "1_1") (pintype "passive"))
      (node (ref "C20") (pin "1") (pinfunction "1_1") (pintype "passive"))
      (node (ref "C23") (pin "1") (pinfunction "1_1") (pintype "passive"))
      (node (ref "C24") (pin "1") (pinfunction "1_1") (pintype "passive"))
      (node (ref "C25") (pin "1") (pinfunction "1_1") (pintype "passive"))
      (node (ref "C29") (pin "1") (pinfunction "1_1") (pintype "passive"))
      (node (ref "C3") (pin "1") (pinfunction "1_1") (pintype "passive"))
      (node (ref "C30") (pin "1") (pinfunction "1_1") (pintype "passive"))
      (node (ref "C37") (pin "1") (pinfunction "1_1") (pintype "passive"))
      (node (ref "C40") (pin "2") (pinfunction "2_2") (pintype "passive"))
      (node (ref "C41") (pin "1") (pinfunction "1_1") (pintype "passive"))
      (node (ref "C44") (pin "2") (pinfunction "2_2") (pintype "passive"))
      (node (ref "C46") (pin "2") (pinfunction "2_2") (pintype "passive"))
      (node (ref "C48") (pin "2") (pinfunction "2_2") (pintype "passive"))
      (node (ref "C49") (pin "2") (pinfunction "2_2") (pintype "passive"))
      (node (ref "C5") (pin "1") (pinfunction "1_1") (pintype "passive"))
      (node (ref "C51") (pin "2") (pinfunction "2_2") (pintype "passive"))
      (node (ref "C52") (pin "1") (pinfunction "1_1") (pintype "passive"))
      (node (ref "C53") (pin "1") (pinfunction "1_1") (pintype "passive"))
      (node (ref "C56") (pin "1") (pinfunction "1_1") (pintype "passive"))
      (node (ref "C57") (pin "PLUS") (pinfunction "+_PLUS") (pintype "passive"))
      (node (ref "C6") (pin "1") (pinfunction "1_1") (pintype "passive"))
      (node (ref "C60") (pin "PLUS") (pinfunction "+_PLUS") (pintype "passive"))
      (node (ref "IC10") (pin "1") (pinfunction "DIR_1") (pintype "input"))
      (node (ref "IC10") (pin "20") (pinfunction "VCC_20") (pintype "power_in"))
      (node (ref "IC11") (pin "1") (pinfunction "DIR_1") (pintype "input"))
      (node (ref "IC11") (pin "20") (pinfunction "VCC_20") (pintype "power_in"))
      (node (ref "IC12") (pin "14") (pinfunction "VCC_14") (pintype "power_in"))
      (node (ref "IC13") (pin "14") (pinfunction "VCC_14") (pintype "power_in"))
      (node (ref "IC2") (pin "117") (pinfunction "__VCCIO7_1_117") (pintype "power_in"))
      (node (ref "IC2") (pin "122") (pinfunction "__VCCIO7_2_122") (pintype "power_in"))
      (node (ref "IC2") (pin "130") (pinfunction "__VCCIO8_1_130") (pintype "power_in"))
      (node (ref "IC2") (pin "139") (pinfunction "__VCCIO8_2_139") (pintype "power_in"))
      (node (ref "IC2") (pin "17") (pinfunction "__VCCIO1_17") (pintype "power_in"))
      (node (ref "IC2") (pin "26") (pinfunction "__VCCIO2_26") (pintype "power_in"))
      (node (ref "IC2") (pin "40") (pinfunction "__VCCIO3_1_40") (pintype "power_in"))
      (node (ref "IC2") (pin "47") (pinfunction "__VCCIO3_2_47") (pintype "power_in"))
      (node (ref "IC2") (pin "56") (pinfunction "__VCCIO4_1_56") (pintype "power_in"))
      (node (ref "IC2") (pin "62") (pinfunction "__VCCIO4_2_62") (pintype "power_in"))
      (node (ref "IC2") (pin "81") (pinfunction "__VCCIO5_81") (pintype "power_in"))
      (node (ref "IC2") (pin "93") (pinfunction "__VCCIO6_93") (pintype "power_in"))
      (node (ref "IC2") (pin "97") (pinfunction "__MSEL2_97") (pintype "bidirectional"))
      (node (ref "IC3") (pin "1") (pinfunction "DIR_1") (pintype "input"))
      (node (ref "IC3") (pin "20") (pinfunction "VCC_20") (pintype "power_in"))
      (node (ref "IC4") (pin "20") (pinfunction "VCC_20") (pintype "power_in"))
      (node (ref "IC7") (pin "5") (pinfunction "VCC_5") (pintype "power_in"))
      (node (ref "IC7") (pin "8") (pinfunction "V3_8") (pintype "passive"))
      (node (ref "IC8") (pin "3") (pinfunction "EN_3") (pintype "input"))
      (node (ref "IC9") (pin "8") (pinfunction "VCC_8") (pintype "power_in"))
      (node (ref "J1") (pin "4") (pinfunction "4_4") (pintype "passive"))
      (node (ref "J2") (pin "4") (pinfunction "VDD_4") (pintype "power_in"))
      (node (ref "L2") (pin "P$2") (pinfunction "2_P$2") (pintype "passive"))
      (node (ref "LED1") (pin "A") (pinfunction "A_A") (pintype "passive"))
      (node (ref "LED2") (pin "A") (pinfunction "A_A") (pintype "passive"))
      (node (ref "LED3") (pin "A") (pinfunction "A_A") (pintype "passive"))
      (node (ref "LED4") (pin "A") (pinfunction "A_A") (pintype "passive"))
      (node (ref "LED5") (pin "A") (pinfunction "A_A") (pintype "passive"))
      (node (ref "LED6") (pin "A") (pinfunction "A_A") (pintype "passive"))
      (node (ref "Q6") (pin "1") (pinfunction "S_1") (pintype "passive"))
      (node (ref "Q6") (pin "4") (pinfunction "S_4") (pintype "passive"))
      (node (ref "R2") (pin "2") (pinfunction "2_2") (pintype "passive"))
      (node (ref "R20") (pin "2") (pinfunction "2_2") (pintype "passive"))
      (node (ref "R24") (pin "1") (pinfunction "1_1") (pintype "passive"))
      (node (ref "R27") (pin "2") (pinfunction "2_2") (pintype "passive"))
      (node (ref "R28") (pin "1") (pinfunction "1_1") (pintype "passive"))
      (node (ref "R3") (pin "2") (pinfunction "2_2") (pintype "passive"))
      (node (ref "R30") (pin "2") (pinfunction "2_2") (pintype "passive"))
      (node (ref "R31") (pin "2") (pinfunction "2_2") (pintype "passive"))
      (node (ref "R32") (pin "2") (pinfunction "2_2") (pintype "passive"))
      (node (ref "R34") (pin "2") (pinfunction "2_2") (pintype "passive"))
      (node (ref "R38") (pin "2") (pinfunction "2_2") (pintype "passive"))
      (node (ref "R4") (pin "2") (pinfunction "2_2") (pintype "passive"))
      (node (ref "R6") (pin "2") (pinfunction "2_2") (pintype "passive"))
      (node (ref "R7") (pin "2") (pinfunction "2_2") (pintype "passive"))
      (node (ref "R8") (pin "2") (pinfunction "2_2") (pintype "passive"))
      (node (ref "R9") (pin "2") (pinfunction "2_2") (pintype "passive"))
      (node (ref "T+3V3") (pin "TP") (pinfunction "TP_TP") (pintype "input"))
      (node (ref "TP2") (pin "TP") (pinfunction "TP_TP") (pintype "input"))
      (node (ref "U$1") (pin "1") (pinfunction "OE_1") (pintype "input"))
      (node (ref "U$1") (pin "4") (pinfunction "VCC_4") (pintype "power_in"))
      (node (ref "U$3") (pin "5") (pinfunction "VCC_5") (pintype "power_in"))
      (node (ref "U$5") (pin "B1") (pinfunction "+3V3_B1") (pintype "power_in"))
      (node (ref "U1") (pin "2") (pinfunction "3V3_2") (pintype "bidirectional"))
    )
    (net (code "4") (name "+5V") (class "Default")
      (node (ref "CONN1") (pin "A3") (pinfunction "+5V_A3") (pintype "power_in"))
      (node (ref "IC1") (pin "5") (pinfunction "VIN_5") (pintype "power_in"))
      (node (ref "IC8") (pin "1") (pinfunction "VIN_1") (pintype "power_in"))
      (node (ref "Q4") (pin "1") (pinfunction "S_1") (pintype "passive"))
      (node (ref "Q4") (pin "4") (pinfunction "S_4") (pintype "passive"))
      (node (ref "Q5") (pin "1") (pinfunction "S_1") (pintype "passive"))
      (node (ref "Q5") (pin "4") (pinfunction "S_4") (pintype "passive"))
      (node (ref "R11") (pin "2") (pinfunction "2_2") (pintype "passive"))
      (node (ref "R12") (pin "2") (pinfunction "2_2") (pintype "passive"))
      (node (ref "R25") (pin "1") (pinfunction "1_1") (pintype "passive"))
      (node (ref "R42") (pin "1") (pinfunction "1_1") (pintype "passive"))
      (node (ref "R5") (pin "1") (pinfunction "1_1") (pintype "passive"))
      (node (ref "R50") (pin "2") (pinfunction "2_2") (pintype "passive"))
      (node (ref "T+5V") (pin "TP") (pinfunction "TP_TP") (pintype "input"))
      (node (ref "U$5") (pin "A1") (pinfunction "+5V_A1") (pintype "power_in"))
    )
    (net (code "5") (name "+9V") (class "Default")
      (node (ref "CONN1") (pin "A4") (pinfunction "+9V_A4") (pintype "power_in"))
      (node (ref "R49") (pin "2") (pinfunction "2_2") (pintype "passive"))
      (node (ref "R53") (pin "2") (pinfunction "2_2") (pintype "passive"))
      (node (ref "R55") (pin "1") (pinfunction "1_1") (pintype "passive"))
      (node (ref "T+9V") (pin "TP") (pinfunction "TP_TP") (pintype "input"))
      (node (ref "T2") (pin "4") (pinfunction "D_4") (pintype "passive"))
    )
    (net (code "6") (name "+12V") (class "Default")
      (node (ref "CONN1") (pin "B22") (pinfunction "+12V_B22") (pintype "power_in"))
      (node (ref "R47") (pin "2") (pinfunction "2_2") (pintype "passive"))
      (node (ref "T+12V") (pin "TP") (pinfunction "TP_TP") (pintype "input"))
      (node (ref "T2") (pin "5") (pinfunction "S_5") (pintype "passive"))
    )
    (net (code "7") (name "/-5V") (class "Default")
      (node (ref "CONN1") (pin "B20") (pinfunction "-5V_B20") (pintype "power_in"))
    )
    (net (code "8") (name "/-12V") (class "Default")
      (node (ref "CONN1") (pin "B23") (pinfunction "-12V_B23") (pintype "power_in"))
    )
    (net (code "9") (name "/2AROMCS") (class "Default")
      (node (ref "CONN1") (pin "A15") (pinfunction "VIDEO_A15") (pintype "bidirectional"))
      (node (ref "Q4") (pin "6") (pinfunction "D_6") (pintype "passive"))
    )
    (net (code "10") (name "/A0") (class "Default")
      (node (ref "CONN1") (pin "A9") (pinfunction "A0_A9") (pintype "bidirectional"))
      (node (ref "RN4") (pin "1") (pinfunction "1_1") (pintype "passive"))
    )
    (net (code "11") (name "/A1") (class "Default")
      (node (ref "CONN1") (pin "A10") (pinfunction "A1_A10") (pintype "bidirectional"))
      (node (ref "RN4") (pin "2") (pinfunction "1_2") (pintype "passive"))
    )
    (net (code "12") (name "/A2") (class "Default")
      (node (ref "CONN1") (pin "A11") (pinfunction "A2_A11") (pintype "bidirectional"))
      (node (ref "RN4") (pin "3") (pinfunction "1_3") (pintype "passive"))
    )
    (net (code "13") (name "/A3") (class "Default")
      (node (ref "CONN1") (pin "A12") (pinfunction "A3_A12") (pintype "bidirectional"))
      (node (ref "RN4") (pin "4") (pinfunction "1_4") (pintype "passive"))
    )
    (net (code "14") (name "/A4") (class "Default")
      (node (ref "CONN1") (pin "A24") (pinfunction "A4_A24") (pintype "bidirectional"))
      (node (ref "RN5") (pin "4") (pinfunction "1_4") (pintype "passive"))
    )
    (net (code "15") (name "/A5") (class "Default")
      (node (ref "CONN1") (pin "A23") (pinfunction "A5_A23") (pintype "bidirectional"))
      (node (ref "RN5") (pin "3") (pinfunction "1_3") (pintype "passive"))
    )
    (net (code "16") (name "/A6") (class "Default")
      (node (ref "CONN1") (pin "A22") (pinfunction "A6_A22") (pintype "bidirectional"))
      (node (ref "RN5") (pin "2") (pinfunction "1_2") (pintype "passive"))
    )
    (net (code "17") (name "/A7") (class "Default")
      (node (ref "CONN1") (pin "A21") (pinfunction "A7_A21") (pintype "bidirectional"))
      (node (ref "RN5") (pin "1") (pinfunction "1_1") (pintype "passive"))
    )
    (net (code "18") (name "/A8") (class "Default")
      (node (ref "CONN1") (pin "B26") (pinfunction "A8_B26") (pintype "bidirectional"))
      (node (ref "RN6") (pin "1") (pinfunction "1_1") (pintype "passive"))
    )
    (net (code "19") (name "/A9") (class "Default")
      (node (ref "CONN1") (pin "A27") (pinfunction "A9_A27") (pintype "bidirectional"))
      (node (ref "RN6") (pin "2") (pinfunction "1_2") (pintype "passive"))
    )
    (net (code "20") (name "/A10") (class "Default")
      (node (ref "CONN1") (pin "B27") (pinfunction "A10_B27") (pintype "bidirectional"))
      (node (ref "RN6") (pin "3") (pinfunction "1_3") (pintype "passive"))
    )
    (net (code "21") (name "/A11") (class "Default")
      (node (ref "CONN1") (pin "A28") (pinfunction "A11_A28") (pintype "bidirectional"))
      (node (ref "RN6") (pin "4") (pinfunction "1_4") (pintype "passive"))
    )
    (net (code "22") (name "/A12") (class "Default")
      (node (ref "CONN1") (pin "A2") (pinfunction "A12_A2") (pintype "bidirectional"))
      (node (ref "RN3") (pin "4") (pinfunction "1_4") (pintype "passive"))
    )
    (net (code "23") (name "/A13") (class "Default")
      (node (ref "CONN1") (pin "B2") (pinfunction "A13_B2") (pintype "bidirectional"))
      (node (ref "RN3") (pin "3") (pinfunction "1_3") (pintype "passive"))
    )
    (net (code "24") (name "/A14") (class "Default")
      (node (ref "CONN1") (pin "A1") (pinfunction "A14_A1") (pintype "bidirectional"))
      (node (ref "RN3") (pin "2") (pinfunction "1_2") (pintype "passive"))
    )
    (net (code "25") (name "/A15") (class "Default")
      (node (ref "CONN1") (pin "B1") (pinfunction "A15_B1") (pintype "bidirectional"))
      (node (ref "RN3") (pin "1") (pinfunction "1_1") (pintype "passive"))
    )
    (net (code "26") (name "/CK") (class "Default")
      (node (ref "CONN1") (pin "A8") (pinfunction "CK_A8") (pintype "bidirectional"))
      (node (ref "RN1") (pin "1") (pinfunction "1_1") (pintype "passive"))
    )
    (net (code "27") (name "/CONF_DONE") (class "Default")
      (node (ref "IC2") (pin "92") (pinfunction "__CONF_DONE_92") (pintype "bidirectional"))
      (node (ref "R27") (pin "1") (pinfunction "1_1") (pintype "passive"))
      (node (ref "U1") (pin "7") (pinfunction "IO35_7") (pintype "input"))
    )
    (net (code "28") (name "/D0") (class "Default")
      (node (ref "CONN1") (pin "B6") (pinfunction "D0_B6") (pintype "bidirectional"))
      (node (ref "RN7") (pin "2") (pinfunction "1_2") (pintype "passive"))
    )
    (net (code "29") (name "/D1") (class "Default")
      (node (ref "CONN1") (pin "B7") (pinfunction "D1_B7") (pintype "bidirectional"))
      (node (ref "RN7") (pin "3") (pinfunction "1_3") (pintype "passive"))
    )
    (net (code "30") (name "/D2") (class "Default")
      (node (ref "CONN1") (pin "B8") (pinfunction "D2_B8") (pintype "bidirectional"))
      (node (ref "RN7") (pin "4") (pinfunction "1_4") (pintype "passive"))
    )
    (net (code "31") (name "/D3") (class "Default")
      (node (ref "CONN1") (pin "B11") (pinfunction "D3_B11") (pintype "bidirectional"))
      (node (ref "RN8") (pin "3") (pinfunction "1_3") (pintype "passive"))
    )
    (net (code "32") (name "/D4") (class "Default")
      (node (ref "CONN1") (pin "B12") (pinfunction "D4_B12") (pintype "bidirectional"))
      (node (ref "RN8") (pin "4") (pinfunction "1_4") (pintype "passive"))
    )
    (net (code "33") (name "/D5") (class "Default")
      (node (ref "CONN1") (pin "B10") (pinfunction "D5_B10") (pintype "bidirectional"))
      (node (ref "RN8") (pin "2") (pinfunction "1_2") (pintype "passive"))
    )
    (net (code "34") (name "/D6") (class "Default")
      (node (ref "CONN1") (pin "B9") (pinfunction "D6_B9") (pintype "bidirectional"))
      (node (ref "RN8") (pin "1") (pinfunction "1_1") (pintype "passive"))
    )
    (net (code "35") (name "/D7") (class "Default")
      (node (ref "CONN1") (pin "B3") (pinfunction "D7_B3") (pintype "bidirectional"))
      (node (ref "RN7") (pin "1") (pinfunction "1_1") (pintype "passive"))
    )
    (net (code "36") (name "/DM") (class "Default")
      (node (ref "R36") (pin "2") (pinfunction "2_2") (pintype "passive"))
      (node (ref "R43") (pin "2") (pinfunction "2_2") (pintype "passive"))
      (node (ref "TV26") (pin "3") (pinfunction "B_3") (pintype "bidirectional"))
      (node (ref "USB2") (pin "D-") (pinfunction "D-_D-") (pintype "bidirectional"))
    )
    (net (code "37") (name "/DP") (class "Default")
      (node (ref "R35") (pin "2") (pinfunction "2_2") (pintype "passive"))
      (node (ref "R57") (pin "2") (pinfunction "2_2") (pintype "passive"))
      (node (ref "TV26") (pin "2") (pinfunction "A_2") (pintype "bidirectional"))
      (node (ref "USB2") (pin "D+") (pinfunction "D+_D+") (pintype "bidirectional"))
    )
    (net (code "38") (name "/D_BUS_DIR") (class "Default")
      (node (ref "IC2") (pin "11") (pinfunction "__IO_8_11") (pintype "bidirectional"))
      (node (ref "IC4") (pin "1") (pinfunction "DIR_1") (pintype "input"))
    )
    (net (code "39") (name "/D_BUS_OE") (class "Default")
      (node (ref "IC2") (pin "7") (pinfunction "__IO_5_7") (pintype "bidirectional"))
      (node (ref "IC4") (pin "19") (pinfunction "G_19") (pintype "input"))
      (node (ref "R24") (pin "2") (pinfunction "2_2") (pintype "passive"))
    )
    (net (code "40") (name "/ESP_EN") (class "Default")
      (node (ref "C1") (pin "2") (pinfunction "2_2") (pintype "passive"))
      (node (ref "R2") (pin "1") (pinfunction "1_1") (pintype "passive"))
      (node (ref "S1") (pin "B2") (pinfunction "2_B2") (pintype "passive"))
      (node (ref "U$3") (pin "1") (pinfunction "PA4_1") (pintype "passive"))
      (node (ref "U1") (pin "3") (pinfunction "EN_3") (pintype "bidirectional"))
    )
    (net (code "41") (name "/ESP_IO0") (class "Default")
      (node (ref "C2") (pin "2") (pinfunction "2_2") (pintype "passive"))
      (node (ref "R3") (pin "1") (pinfunction "1_1") (pintype "passive"))
      (node (ref "S2") (pin "B2") (pinfunction "2_B2") (pintype "passive"))
      (node (ref "U$3") (pin "3") (pinfunction "PA6_3") (pintype "passive"))
      (node (ref "U1") (pin "25") (pinfunction "IO0_25") (pintype "bidirectional"))
    )
    (net (code "42") (name "/ESP_IO26") (class "Default")
      (node (ref "IC2") (pin "138") (pinfunction "__IO_80_138") (pintype "bidirectional"))
      (node (ref "U1") (pin "11") (pinfunction "IO26_11") (pintype "bidirectional"))
    )
    (net (code "43") (name "/ESP_IO27") (class "Default")
      (node (ref "IC2") (pin "141") (pinfunction "__IO_81_141") (pintype "bidirectional"))
      (node (ref "U1") (pin "12") (pinfunction "IO27_12") (pintype "bidirectional"))
    )
    (net (code "44") (name "/ESP_MISO") (class "Default")
      (node (ref "IC2") (pin "6") (pinfunction "__IO_4/DATA/ADSO_6") (pintype "bidirectional"))
      (node (ref "U1") (pin "31") (pinfunction "IO19_31") (pintype "bidirectional"))
    )
    (net (code "45") (name "/ESP_MOSI") (class "Default")
      (node (ref "IC2") (pin "13") (pinfunction "__DATA0_13") (pintype "bidirectional"))
      (node (ref "U1") (pin "37") (pinfunction "IO23_37") (pintype "bidirectional"))
    )
    (net (code "46") (name "/ESP_NCS0") (class "Default")
      (node (ref "IC2") (pin "3") (pinfunction "__IO_3_3") (pintype "bidirectional"))
      (node (ref "U1") (pin "29") (pinfunction "IO5_29") (pintype "bidirectional"))
    )
    (net (code "47") (name "/ESP_QDH") (class "Default")
      (node (ref "IC2") (pin "1") (pinfunction "__IO_1_1") (pintype "bidirectional"))
      (node (ref "U1") (pin "33") (pinfunction "IO21_33") (pintype "bidirectional"))
    )
    (net (code "48") (name "/ESP_QWP") (class "Default")
      (node (ref "IC2") (pin "143") (pinfunction "__IO_83_143") (pintype "bidirectional"))
      (node (ref "U1") (pin "36") (pinfunction "IO22_36") (pintype "bidirectional"))
    )
    (net (code "49") (name "/ESP_RX") (class "Default")
      (node (ref "IC7") (pin "6") (pinfunction "TX_6") (pintype "output"))
      (node (ref "U$3") (pin "6") (pinfunction "PA3_6") (pintype "passive"))
      (node (ref "U1") (pin "34") (pinfunction "RXD0_34") (pintype "bidirectional"))
    )
    (net (code "50") (name "/ESP_SCK") (class "Default")
      (node (ref "IC2") (pin "12") (pinfunction "__DCLK_12") (pintype "input"))
      (node (ref "IC2") (pin "23") (pinfunction "__CLK1_23") (pintype "input"))
      (node (ref "U1") (pin "30") (pinfunction "IO18_30") (pintype "bidirectional"))
    )
    (net (code "51") (name "/ESP_TX") (class "Default")
      (node (ref "IC7") (pin "7") (pinfunction "RX_7") (pintype "input"))
      (node (ref "U1") (pin "35") (pinfunction "TXD0_35") (pintype "bidirectional"))
    )
    (net (code "52") (name "/EXT0") (class "Default")
      (node (ref "IC2") (pin "135") (pinfunction "__IO_77_135") (pintype "bidirectional"))
      (node (ref "U$5") (pin "B4") (pinfunction "E0_B4") (pintype "bidirectional"))
    )
    (net (code "53") (name "/EXT1") (class "Default")
      (node (ref "IC2") (pin "133") (pinfunction "__IO_76_133") (pintype "bidirectional"))
      (node (ref "U$5") (pin "B5") (pinfunction "E1_B5") (pintype "bidirectional"))
    )
    (net (code "54") (name "/EXT2") (class "Default")
      (node (ref "IC2") (pin "128") (pinfunction "__IO_73_128") (pintype "bidirectional"))
      (node (ref "U$5") (pin "B6") (pinfunction "E2_B6") (pintype "bidirectional"))
    )
    (net (code "55") (name "/EXT3") (class "Default")
      (node (ref "IC2") (pin "127") (pinfunction "__IO_72_127") (pintype "bidirectional"))
      (node (ref "U$5") (pin "B7") (pinfunction "E3_B7") (pintype "bidirectional"))
    )
    (net (code "56") (name "/EXT4") (class "Default")
      (node (ref "IC2") (pin "126") (pinfunction "__IO_71_126") (pintype "bidirectional"))
      (node (ref "U$5") (pin "B8") (pinfunction "E4_B8") (pintype "bidirectional"))
    )
    (net (code "57") (name "/EXT5") (class "Default")
      (node (ref "IC2") (pin "125") (pinfunction "__IO_70_125") (pintype "bidirectional"))
      (node (ref "U$5") (pin "B9") (pinfunction "E5_B9") (pintype "bidirectional"))
    )
    (net (code "58") (name "/EXT6") (class "Default")
      (node (ref "IC2") (pin "124") (pinfunction "__IO_69_124") (pintype "bidirectional"))
      (node (ref "U$5") (pin "B10") (pinfunction "E6_B10") (pintype "bidirectional"))
    )
    (net (code "59") (name "/EXT7") (class "Default")
      (node (ref "IC2") (pin "121") (pinfunction "__IO_68_121") (pintype "bidirectional"))
      (node (ref "U$5") (pin "A10") (pinfunction "E7_A10") (pintype "bidirectional"))
    )
    (net (code "60") (name "/EXT8") (class "Default")
      (node (ref "IC2") (pin "114") (pinfunction "__IO_64_114") (pintype "bidirectional"))
      (node (ref "U$5") (pin "A9") (pinfunction "E8_A9") (pintype "bidirectional"))
    )
    (net (code "61") (name "/EXT9") (class "Default")
      (node (ref "IC2") (pin "115") (pinfunction "__IO_65_115") (pintype "bidirectional"))
      (node (ref "U$5") (pin "A8") (pinfunction "E9_A8") (pintype "bidirectional"))
    )
    (net (code "62") (name "/EXT10") (class "Default")
      (node (ref "IC2") (pin "119") (pinfunction "__IO_66_119") (pintype "bidirectional"))
      (node (ref "U$5") (pin "A7") (pinfunction "E10_A7") (pintype "bidirectional"))
    )
    (net (code "63") (name "/EXT11") (class "Default")
      (node (ref "IC2") (pin "120") (pinfunction "__IO_67_120") (pintype "bidirectional"))
      (node (ref "U$5") (pin "A6") (pinfunction "E11_A6") (pintype "bidirectional"))
    )
    (net (code "64") (name "/EXT12") (class "Default")
      (node (ref "IC2") (pin "142") (pinfunction "__IO_82_142") (pintype "bidirectional"))
      (node (ref "U$5") (pin "A5") (pinfunction "E12_A5") (pintype "bidirectional"))
    )
    (net (code "65") (name "/EXT13") (class "Default")
      (node (ref "IC2") (pin "144") (pinfunction "__IO_84_144") (pintype "bidirectional"))
      (node (ref "U$5") (pin "A4") (pinfunction "E13_A4") (pintype "bidirectional"))
    )
    (net (code "66") (name "/FLED0") (class "Default")
      (node (ref "IC2") (pin "76") (pinfunction "__IO_44_76") (pintype "bidirectional"))
      (node (ref "R41") (pin "2") (pinfunction "2_2") (pintype "passive"))
    )
    (net (code "67") (name "/FLED1") (class "Default")
      (node (ref "IC2") (pin "77") (pinfunction "__IO_45_77") (pintype "bidirectional"))
      (node (ref "R40") (pin "2") (pinfunction "2_2") (pintype "passive"))
    )
    (net (code "68") (name "/FLED2") (class "Default")
      (node (ref "IC2") (pin "80") (pinfunction "__IO_46_80") (pintype "bidirectional"))
      (node (ref "R39") (pin "2") (pinfunction "2_2") (pintype "passive"))
    )
    (net (code "69") (name "/FORCE_2AROMCS") (class "Default")
      (node (ref "IC13") (pin "5") (pinfunction "I_5") (pintype "input"))
      (node (ref "IC2") (pin "10") (pinfunction "__IO_7_10") (pintype "bidirectional"))
    )
    (net (code "70") (name "/FORCE_INT") (class "Default")
      (node (ref "IC13") (pin "1") (pinfunction "I_1") (pintype "input"))
      (node (ref "IC2") (pin "53") (pinfunction "__IO_26_53") (pintype "bidirectional"))
    )
    (net (code "71") (name "/FORCE_IORQULA") (class "Default")
      (node (ref "IC13") (pin "9") (pinfunction "I_9") (pintype "input"))
      (node (ref "IC2") (pin "136") (pinfunction "__IO_78_136") (pintype "bidirectional"))
    )
    (net (code "72") (name "/FORCE_NMI") (class "Default")
      (node (ref "IC13") (pin "3") (pinfunction "I_3") (pintype "input"))
      (node (ref "IC2") (pin "137") (pinfunction "__IO_79_137") (pintype "bidirectional"))
    )
    (net (code "73") (name "/FORCE_RESET") (class "Default")
      (node (ref "IC2") (pin "67") (pinfunction "__IO_35_67") (pintype "bidirectional"))
      (node (ref "Q1") (pin "1") (pinfunction "G_1") (pintype "passive"))
    )
    (net (code "74") (name "/FORCE_ROMCS") (class "Default")
      (node (ref "IC13") (pin "13") (pinfunction "I_13") (pintype "input"))
      (node (ref "IC2") (pin "132") (pinfunction "__IO_75_132") (pintype "bidirectional"))
    )
    (net (code "75") (name "/FORCE_WAIT") (class "Default")
      (node (ref "IC13") (pin "11") (pinfunction "I_11") (pintype "input"))
      (node (ref "IC2") (pin "129") (pinfunction "__IO_74_129") (pintype "bidirectional"))
    )
    (net (code "76") (name "/FR1") (class "Default")
      (node (ref "IC13") (pin "12") (pinfunction "O_12") (pintype "open_collector"))
      (node (ref "Q5") (pin "2") (pinfunction "G_2") (pintype "passive"))
      (node (ref "Q5") (pin "5") (pinfunction "G_5") (pintype "passive"))
      (node (ref "R5") (pin "2") (pinfunction "2_2") (pintype "passive"))
    )
    (net (code "77") (name "/FR2") (class "Default")
      (node (ref "IC13") (pin "8") (pinfunction "O_8") (pintype "open_collector"))
      (node (ref "Q4") (pin "5") (pinfunction "G_5") (pintype "passive"))
      (node (ref "R42") (pin "2") (pinfunction "2_2") (pintype "passive"))
    )
    (net (code "78") (name "/INT") (class "Default")
      (node (ref "CONN1") (pin "B13") (pinfunction "INT_B13") (pintype "bidirectional"))
      (node (ref "IC13") (pin "2") (pinfunction "O_2") (pintype "open_collector"))
      (node (ref "RN1") (pin "2") (pinfunction "1_2") (pintype "passive"))
    )
    (net (code "79") (name "/IO6") (class "Default")
      (node (ref "IC2") (pin "8") (pinfunction "__IO_6/FLASH_NCS/NCSO_8") (pintype "bidirectional"))
      (node (ref "U1") (pin "28") (pinfunction "IO17_28") (pintype "bidirectional"))
    )
    (net (code "80") (name "/IORQ") (class "Default")
      (node (ref "CONN1") (pin "B17") (pinfunction "IORQ_B17") (pintype "bidirectional"))
      (node (ref "RN1") (pin "4") (pinfunction "1_4") (pintype "passive"))
    )
    (net (code "81") (name "/IORQULA") (class "Default")
      (node (ref "CONN1") (pin "A13") (pinfunction "IORQULA_A13") (pintype "bidirectional"))
      (node (ref "Q4") (pin "3") (pinfunction "D_3") (pintype "passive"))
    )
    (net (code "82") (name "/LED1") (class "Default")
      (node (ref "R21") (pin "2") (pinfunction "2_2") (pintype "passive"))
      (node (ref "U1") (pin "8") (pinfunction "IO32_8") (pintype "bidirectional"))
    )
    (net (code "83") (name "/LED2") (class "Default")
      (node (ref "IC2") (pin "2") (pinfunction "__IO_2_2") (pintype "bidirectional"))
      (node (ref "R22") (pin "2") (pinfunction "2_2") (pintype "passive"))
    )
    (net (code "84") (name "/M1") (class "Default")
      (node (ref "CONN1") (pin "B24") (pinfunction "M1_B24") (pintype "bidirectional"))
      (node (ref "RN2") (pin "3") (pinfunction "1_3") (pintype "passive"))
    )
    (net (code "85") (name "/MREQ") (class "Default")
      (node (ref "CONN1") (pin "B16") (pinfunction "MREQ_B16") (pintype "bidirectional"))
      (node (ref "RN1") (pin "3") (pinfunction "1_3") (pintype "passive"))
    )
    (net (code "86") (name "/NCONFIG") (class "Default")
      (node (ref "IC2") (pin "14") (pinfunction "__NCONFIG_14") (pintype "bidirectional"))
      (node (ref "R7") (pin "1") (pinfunction "1_1") (pintype "passive"))
      (node (ref "U1") (pin "10") (pinfunction "IO25_10") (pintype "bidirectional"))
    )
    (net (code "87") (name "/NMI") (class "Default")
      (node (ref "CONN1") (pin "B14") (pinfunction "NMI_B14") (pintype "bidirectional"))
      (node (ref "IC13") (pin "4") (pinfunction "O_4") (pintype "open_collector"))
    )
    (net (code "88") (name "/NSTATUS") (class "Default")
      (node (ref "IC2") (pin "9") (pinfunction "__NSTATUS_9") (pintype "bidirectional"))
      (node (ref "R6") (pin "1") (pinfunction "1_1") (pintype "passive"))
      (node (ref "U1") (pin "27") (pinfunction "IO16_27") (pintype "bidirectional"))
    )
    (net (code "89") (name "/PEN1") (class "Default")
      (node (ref "IC1") (pin "4") (pinfunction "NEN_4") (pintype "input"))
      (node (ref "R37") (pin "1") (pinfunction "1_1") (pintype "passive"))
    )
    (net (code "90") (name "/PULLUP_EN") (class "Default")
      (node (ref "Q6") (pin "2") (pinfunction "G_2") (pintype "passive"))
      (node (ref "Q6") (pin "5") (pinfunction "G_5") (pintype "passive"))
      (node (ref "R28") (pin "2") (pinfunction "2_2") (pintype "passive"))
      (node (ref "U1") (pin "9") (pinfunction "IO33_9") (pintype "bidirectional"))
    )
    (net (code "91") (name "/RAMCLK") (class "Default")
      (node (ref "IC2") (pin "84") (pinfunction "__IO_48_84") (pintype "bidirectional"))
      (node (ref "IC9") (pin "6") (pinfunction "SCK_6") (pintype "input"))
    )
    (net (code "92") (name "/RAMD0") (class "Default")
      (node (ref "IC2") (pin "83") (pinfunction "__IO_47_83") (pintype "bidirectional"))
      (node (ref "IC9") (pin "5") (pinfunction "SI/SIO[0]_5") (pintype "bidirectional"))
    )
    (net (code "93") (name "/RAMD1") (class "Default")
      (node (ref "IC2") (pin "87") (pinfunction "__IO_51_87") (pintype "bidirectional"))
      (node (ref "IC9") (pin "2") (pinfunction "SO/SIO[1]_2") (pintype "bidirectional"))
    )
    (net (code "94") (name "/RAMD2") (class "Default")
      (node (ref "IC2") (pin "86") (pinfunction "__IO_50_86") (pintype "bidirectional"))
      (node (ref "IC9") (pin "3") (pinfunction "SIO[2]_3") (pintype "bidirectional"))
    )
    (net (code "95") (name "/RAMD3") (class "Default")
      (node (ref "IC2") (pin "85") (pinfunction "__IO_49_85") (pintype "bidirectional"))
      (node (ref "IC9") (pin "7") (pinfunction "SIO[3]_7") (pintype "bidirectional"))
    )
    (net (code "96") (name "/RAMNCS") (class "Default")
      (node (ref "IC2") (pin "98") (pinfunction "__IO_52_98") (pintype "bidirectional"))
      (node (ref "IC9") (pin "1") (pinfunction "NCS_1") (pintype "input"))
    )
    (net (code "97") (name "/RCV") (class "Default")
      (node (ref "IC12") (pin "3") (pinfunction "RCV_3") (pintype "output"))
      (node (ref "IC2") (pin "103") (pinfunction "__IO_56_103") (pintype "bidirectional"))
    )
    (net (code "98") (name "/RD") (class "Default")
      (node (ref "CONN1") (pin "B18") (pinfunction "RD_B18") (pintype "bidirectional"))
      (node (ref "RN2") (pin "1") (pinfunction "1_1") (pintype "passive"))
    )
    (net (code "99") (name "/RESET") (class "Default")
      (node (ref "CONN1") (pin "A20") (pinfunction "RESET_A20") (pintype "bidirectional"))
      (node (ref "Q1") (pin "3") (pinfunction "D_3") (pintype "passive"))
    )
    (net (code "100") (name "/RFSH") (class "Default")
      (node (ref "CONN1") (pin "B25") (pinfunction "RFSH_B25") (pintype "bidirectional"))
      (node (ref "RN2") (pin "4") (pinfunction "1_4") (pintype "passive"))
    )
    (net (code "101") (name "/ROMCS") (class "Default")
      (node (ref "CONN1") (pin "A25") (pinfunction "ROMCS_A25") (pintype "bidirectional"))
      (node (ref "Q5") (pin "6") (pinfunction "D_6") (pintype "passive"))
    )
    (net (code "102") (name "/ROMCS2") (class "Default")
      (node (ref "CONN1") (pin "B4") (pinfunction "NC3_B4") (pintype "passive"))
      (node (ref "Q5") (pin "3") (pinfunction "D_3") (pintype "passive"))
    )
    (net (code "103") (name "/RTS") (class "Default")
      (node (ref "IC7") (pin "4") (pinfunction "RTS_4") (pintype "output"))
      (node (ref "U$3") (pin "4") (pinfunction "PA5_4") (pintype "passive"))
    )
    (net (code "104") (name "/SDMMC_CK") (class "Default")
      (node (ref "J2") (pin "5") (pinfunction "CLK_5") (pintype "passive"))
      (node (ref "R32") (pin "1") (pinfunction "1_1") (pintype "passive"))
      (node (ref "U1") (pin "13") (pinfunction "IO14_13") (pintype "bidirectional"))
    )
    (net (code "105") (name "/SDMMC_CMD") (class "Default")
      (node (ref "J2") (pin "3") (pinfunction "CMD_3") (pintype "passive"))
      (node (ref "R31") (pin "1") (pinfunction "1_1") (pintype "passive"))
      (node (ref "U1") (pin "23") (pinfunction "IO15_23") (pintype "bidirectional"))
    )
    (net (code "106") (name "/SDMMC_D0") (class "Default")
      (node (ref "J2") (pin "7") (pinfunction "DAT0_7") (pintype "passive"))
      (node (ref "R33") (pin "2") (pinfunction "2_2") (pintype "passive"))
      (node (ref "U1") (pin "24") (pinfunction "IO2_24") (pintype "bidirectional"))
    )
    (net (code "107") (name "/SDMMC_D1") (class "Default")
      (node (ref "J2") (pin "8") (pinfunction "DAT1_8") (pintype "passive"))
      (node (ref "R34") (pin "1") (pinfunction "1_1") (pintype "passive"))
      (node (ref "U1") (pin "26") (pinfunction "IO4_26") (pintype "bidirectional"))
    )
    (net (code "108") (name "/SDMMC_D2") (class "Default")
      (node (ref "J2") (pin "1") (pinfunction "DAT2_1") (pintype "passive"))
      (node (ref "R29") (pin "2") (pinfunction "2_2") (pintype "passive"))
      (node (ref "U1") (pin "14") (pinfunction "IO12_14") (pintype "bidirectional"))
    )
    (net (code "109") (name "/SDMMC_D3") (class "Default")
      (node (ref "J2") (pin "2") (pinfunction "CD/DAT3^2_2") (pintype "passive"))
      (node (ref "R30") (pin "1") (pinfunction "1_1") (pintype "passive"))
      (node (ref "U1") (pin "16") (pinfunction "IO13_16") (pintype "bidirectional"))
    )
    (net (code "110") (name "/SW1") (class "Default")
      (node (ref "C42") (pin "1") (pinfunction "1_1") (pintype "passive"))
      (node (ref "IC5") (pin "3") (pinfunction "SW_3") (pintype "passive"))
      (node (ref "L1") (pin "P$1") (pinfunction "1_P$1") (pintype "passive"))
    )
    (net (code "111") (name "/SW2") (class "Default")
      (node (ref "C43") (pin "1") (pinfunction "1_1") (pintype "passive"))
      (node (ref "IC6") (pin "3") (pinfunction "SW_3") (pintype "passive"))
      (node (ref "L2") (pin "P$1") (pinfunction "1_P$1") (pintype "passive"))
    )
    (net (code "112") (name "/SWITCH") (class "Default")
      (node (ref "R4") (pin "1") (pinfunction "1_1") (pintype "passive"))
      (node (ref "S3") (pin "B2") (pinfunction "2_B2") (pintype "passive"))
      (node (ref "U1") (pin "6") (pinfunction "IO34_6") (pintype "input"))
    )
    (net (code "113") (name "/TCK") (class "Default")
      (node (ref "IC2") (pin "16") (pinfunction "__TCK_16") (pintype "bidirectional"))
      (node (ref "J1") (pin "1") (pinfunction "1_1") (pintype "passive"))
      (node (ref "R10") (pin "1") (pinfunction "1_1") (pintype "passive"))
    )
    (net (code "114") (name "/TDI") (class "Default")
      (node (ref "IC2") (pin "15") (pinfunction "__TDI_15") (pintype "bidirectional"))
      (node (ref "J1") (pin "9") (pinfunction "9_9") (pintype "passive"))
    )
    (net (code "115") (name "/TDO") (class "Default")
      (node (ref "IC2") (pin "20") (pinfunction "__TDO_20") (pintype "bidirectional"))
      (node (ref "J1") (pin "3") (pinfunction "3_3") (pintype "passive"))
      (node (ref "R8") (pin "1") (pinfunction "1_1") (pintype "passive"))
    )
    (net (code "116") (name "/TMS") (class "Default")
      (node (ref "IC2") (pin "18") (pinfunction "__TMS_18") (pintype "bidirectional"))
      (node (ref "J1") (pin "5") (pinfunction "5_5") (pintype "passive"))
      (node (ref "R9") (pin "1") (pinfunction "1_1") (pintype "passive"))
    )
    (net (code "117") (name "/USB_FLT") (class "Default")
      (node (ref "IC1") (pin "3") (pinfunction "FAULT_3") (pintype "output"))
      (node (ref "IC2") (pin "112") (pinfunction "__IO_62_112") (pintype "bidirectional"))
      (node (ref "R38") (pin "1") (pinfunction "1_1") (pintype "passive"))
    )
    (net (code "118") (name "/USB_MODE") (class "Default")
      (node (ref "IC12") (pin "1") (pinfunction "MODE_1") (pintype "input"))
      (node (ref "IC2") (pin "105") (pinfunction "__IO_58_105") (pintype "bidirectional"))
    )
    (net (code "119") (name "/USB_OE") (class "Default")
      (node (ref "IC12") (pin "2") (pinfunction "OE_2") (pintype "input"))
      (node (ref "IC2") (pin "104") (pinfunction "__IO_57_104") (pintype "bidirectional"))
    )
    (net (code "120") (name "/USB_PWREN") (class "Default")
      (node (ref "IC2") (pin "113") (pinfunction "__IO_63_113") (pintype "bidirectional"))
      (node (ref "R37") (pin "2") (pinfunction "2_2") (pintype "passive"))
    )
    (net (code "121") (name "/USB_SPEED") (class "Default")
      (node (ref "IC12") (pin "9") (pinfunction "SPEED_9") (pintype "input"))
      (node (ref "IC2") (pin "106") (pinfunction "__IO_59_106") (pintype "bidirectional"))
    )
    (net (code "122") (name "/USB_SUSPEND") (class "Default")
      (node (ref "IC12") (pin "6") (pinfunction "SUSPND_6") (pintype "input"))
      (node (ref "IC2") (pin "99") (pinfunction "__IO_53_99") (pintype "bidirectional"))
    )
    (net (code "123") (name "/VBUS") (class "Default")
      (node (ref "C59") (pin "+") (pinfunction "+_+") (pintype "passive"))
      (node (ref "IC1") (pin "1") (pinfunction "VOUT_1") (pintype "power_in"))
      (node (ref "TV26") (pin "4") (pinfunction "C_4") (pintype "bidirectional"))
      (node (ref "USB2") (pin "VBUS") (pinfunction "VBUS_VBUS") (pintype "bidirectional"))
    )
    (net (code "124") (name "/VM") (class "Default")
      (node (ref "IC12") (pin "5") (pinfunction "VM_5") (pintype "output"))
      (node (ref "IC2") (pin "100") (pinfunction "__IO_54_100") (pintype "bidirectional"))
    )
    (net (code "125") (name "/VMO") (class "Default")
      (node (ref "IC12") (pin "13") (pinfunction "VMO_13") (pintype "input"))
      (node (ref "IC2") (pin "111") (pinfunction "__IO_61_111") (pintype "bidirectional"))
    )
    (net (code "126") (name "/VP") (class "Default")
      (node (ref "IC12") (pin "4") (pinfunction "VP_4") (pintype "output"))
      (node (ref "IC2") (pin "101") (pinfunction "__IO_55_101") (pintype "bidirectional"))
    )
    (net (code "127") (name "/VPO") (class "Default")
      (node (ref "IC12") (pin "12") (pinfunction "VPO_12") (pintype "input"))
      (node (ref "IC2") (pin "110") (pinfunction "__IO_60_110") (pintype "bidirectional"))
    )
    (net (code "128") (name "/VSENS") (class "Default")
      (node (ref "R46") (pin "1") (pinfunction "1_1") (pintype "passive"))
      (node (ref "U1") (pin "4") (pinfunction "SENSOR_VP_4") (pintype "input"))
    )
    (net (code "129") (name "/VSWITCH") (class "Default")
      (node (ref "C31") (pin "2") (pinfunction "2_2") (pintype "passive"))
      (node (ref "C32") (pin "2") (pinfunction "2_2") (pintype "passive"))
      (node (ref "C33") (pin "2") (pinfunction "2_2") (pintype "passive"))
      (node (ref "C34") (pin "2") (pinfunction "2_2") (pintype "passive"))
      (node (ref "C54") (pin "2") (pinfunction "2_2") (pintype "passive"))
      (node (ref "IC5") (pin "2") (pinfunction "IN_2") (pintype "power_in"))
      (node (ref "IC6") (pin "2") (pinfunction "IN_2") (pintype "power_in"))
      (node (ref "R44") (pin "2") (pinfunction "2_2") (pintype "passive"))
      (node (ref "R51") (pin "2") (pinfunction "2_2") (pintype "passive"))
      (node (ref "T2") (pin "2") (pinfunction "S_2") (pintype "passive"))
      (node (ref "T2") (pin "6") (pinfunction "D_6") (pintype "passive"))
      (node (ref "TP5") (pin "TP") (pinfunction "TP_TP") (pintype "input"))
    )
    (net (code "130") (name "/WAIT") (class "Default")
      (node (ref "CONN1") (pin "B21") (pinfunction "WAIT_B21") (pintype "bidirectional"))
      (node (ref "IC13") (pin "10") (pinfunction "O_10") (pintype "open_collector"))
    )
    (net (code "131") (name "/WR") (class "Default")
      (node (ref "CONN1") (pin "B19") (pinfunction "WR_B19") (pintype "bidirectional"))
      (node (ref "RN2") (pin "2") (pinfunction "1_2") (pintype "passive"))
    )
    (net (code "132") (name "/XCK") (class "Default")
      (node (ref "IC2") (pin "54") (pinfunction "__IO_27_54") (pintype "bidirectional"))
      (node (ref "IC3") (pin "18") (pinfunction "B1_18") (pintype "bidirectional"))
    )
    (net (code "133") (name "/XD0") (class "Default")
      (node (ref "IC2") (pin "43") (pinfunction "__IO_19_43") (pintype "bidirectional"))
      (node (ref "IC4") (pin "17") (pinfunction "B2_17") (pintype "bidirectional"))
    )
    (net (code "134") (name "/XD1") (class "Default")
      (node (ref "IC2") (pin "44") (pinfunction "__IO_20_44") (pintype "bidirectional"))
      (node (ref "IC4") (pin "16") (pinfunction "B3_16") (pintype "bidirectional"))
    )
    (net (code "135") (name "/XD2") (class "Default")
      (node (ref "IC2") (pin "46") (pinfunction "__IO_21_46") (pintype "bidirectional"))
      (node (ref "IC4") (pin "15") (pinfunction "B4_15") (pintype "bidirectional"))
    )
    (net (code "136") (name "/XD3") (class "Default")
      (node (ref "IC2") (pin "51") (pinfunction "__IO_24_51") (pintype "bidirectional"))
      (node (ref "IC4") (pin "12") (pinfunction "B7_12") (pintype "bidirectional"))
    )
    (net (code "137") (name "/XD4") (class "Default")
      (node (ref "IC2") (pin "52") (pinfunction "__IO_25_52") (pintype "bidirectional"))
      (node (ref "IC4") (pin "11") (pinfunction "B8_11") (pintype "bidirectional"))
    )
    (net (code "138") (name "/XD5") (class "Default")
      (node (ref "IC2") (pin "50") (pinfunction "__IO_23_50") (pintype "bidirectional"))
      (node (ref "IC4") (pin "13") (pinfunction "B6_13") (pintype "bidirectional"))
    )
    (net (code "139") (name "/XD6") (class "Default")
      (node (ref "IC2") (pin "49") (pinfunction "__IO_22_49") (pintype "bidirectional"))
      (node (ref "IC4") (pin "14") (pinfunction "B5_14") (pintype "bidirectional"))
    )
    (net (code "140") (name "/XD7") (class "Default")
      (node (ref "IC2") (pin "42") (pinfunction "__IO_18_42") (pintype "bidirectional"))
      (node (ref "IC4") (pin "18") (pinfunction "B1_18") (pintype "bidirectional"))
    )
    (net (code "141") (name "/XINT") (class "Default")
      (node (ref "IC2") (pin "55") (pinfunction "__IO_28_55") (pintype "bidirectional"))
      (node (ref "IC3") (pin "17") (pinfunction "B2_17") (pintype "bidirectional"))
    )
    (net (code "142") (name "/XIORQ") (class "Default")
      (node (ref "IC2") (pin "59") (pinfunction "__IO_30_59") (pintype "bidirectional"))
      (node (ref "IC3") (pin "15") (pinfunction "B4_15") (pintype "bidirectional"))
    )
    (net (code "143") (name "/XM1") (class "Default")
      (node (ref "IC2") (pin "65") (pinfunction "__IO_33_65") (pintype "bidirectional"))
      (node (ref "IC3") (pin "12") (pinfunction "B7_12") (pintype "bidirectional"))
    )
    (net (code "144") (name "/XMREQ") (class "Default")
      (node (ref "IC2") (pin "58") (pinfunction "__IO_29_58") (pintype "bidirectional"))
      (node (ref "IC3") (pin "16") (pinfunction "B3_16") (pintype "bidirectional"))
    )
    (net (code "145") (name "/XRD") (class "Default")
      (node (ref "IC2") (pin "60") (pinfunction "__IO_31_60") (pintype "bidirectional"))
      (node (ref "IC3") (pin "14") (pinfunction "B5_14") (pintype "bidirectional"))
    )
    (net (code "146") (name "/XRFSH") (class "Default")
      (node (ref "IC2") (pin "66") (pinfunction "__IO_34_66") (pintype "bidirectional"))
      (node (ref "IC3") (pin "11") (pinfunction "B8_11") (pintype "bidirectional"))
    )
    (net (code "147") (name "/XWR") (class "Default")
      (node (ref "IC2") (pin "64") (pinfunction "__IO_32_64") (pintype "bidirectional"))
      (node (ref "IC3") (pin "13") (pinfunction "B6_13") (pintype "bidirectional"))
    )
    (net (code "148") (name "/ZX_A0") (class "Default")
      (node (ref "IC10") (pin "14") (pinfunction "B5_14") (pintype "bidirectional"))
      (node (ref "IC2") (pin "33") (pinfunction "__IO_14_33") (pintype "bidirectional"))
    )
    (net (code "149") (name "/ZX_A1") (class "Default")
      (node (ref "IC10") (pin "13") (pinfunction "B6_13") (pintype "bidirectional"))
      (node (ref "IC2") (pin "34") (pinfunction "__IO_15_34") (pintype "bidirectional"))
    )
    (net (code "150") (name "/ZX_A2") (class "Default")
      (node (ref "IC10") (pin "12") (pinfunction "B7_12") (pintype "bidirectional"))
      (node (ref "IC2") (pin "38") (pinfunction "__IO_16_38") (pintype "bidirectional"))
    )
    (net (code "151") (name "/ZX_A3") (class "Default")
      (node (ref "IC10") (pin "11") (pinfunction "B8_11") (pintype "bidirectional"))
      (node (ref "IC2") (pin "39") (pinfunction "__IO_17_39") (pintype "bidirectional"))
    )
    (net (code "152") (name "/ZX_A4") (class "Default")
      (node (ref "IC11") (pin "15") (pinfunction "B4_15") (pintype "bidirectional"))
      (node (ref "IC2") (pin "71") (pinfunction "__IO_39_71") (pintype "bidirectional"))
    )
    (net (code "153") (name "/ZX_A5") (class "Default")
      (node (ref "IC11") (pin "16") (pinfunction "B3_16") (pintype "bidirectional"))
      (node (ref "IC2") (pin "70") (pinfunction "__IO_38_70") (pintype "bidirectional"))
    )
    (net (code "154") (name "/ZX_A6") (class "Default")
      (node (ref "IC11") (pin "17") (pinfunction "B2_17") (pintype "bidirectional"))
      (node (ref "IC2") (pin "69") (pinfunction "__IO_37_69") (pintype "bidirectional"))
    )
    (net (code "155") (name "/ZX_A7") (class "Default")
      (node (ref "IC11") (pin "18") (pinfunction "B1_18") (pintype "bidirectional"))
      (node (ref "IC2") (pin "68") (pinfunction "__IO_36_68") (pintype "bidirectional"))
    )
    (net (code "156") (name "/ZX_A8") (class "Default")
      (node (ref "IC11") (pin "14") (pinfunction "B5_14") (pintype "bidirectional"))
      (node (ref "IC2") (pin "72") (pinfunction "__IO_40_72") (pintype "bidirectional"))
    )
    (net (code "157") (name "/ZX_A9") (class "Default")
      (node (ref "IC11") (pin "13") (pinfunction "B6_13") (pintype "bidirectional"))
      (node (ref "IC2") (pin "73") (pinfunction "__IO_41_73") (pintype "bidirectional"))
    )
    (net (code "158") (name "/ZX_A10") (class "Default")
      (node (ref "IC11") (pin "12") (pinfunction "B7_12") (pintype "bidirectional"))
      (node (ref "IC2") (pin "74") (pinfunction "__IO_42_74") (pintype "bidirectional"))
    )
    (net (code "159") (name "/ZX_A11") (class "Default")
      (node (ref "IC11") (pin "11") (pinfunction "B8_11") (pintype "bidirectional"))
      (node (ref "IC2") (pin "75") (pinfunction "__IO_43_75") (pintype "bidirectional"))
    )
    (net (code "160") (name "/ZX_A12") (class "Default")
      (node (ref "IC10") (pin "15") (pinfunction "B4_15") (pintype "bidirectional"))
      (node (ref "IC2") (pin "32") (pinfunction "__IO_13_32") (pintype "bidirectional"))
    )
    (net (code "161") (name "/ZX_A13") (class "Default")
      (node (ref "IC10") (pin "16") (pinfunction "B3_16") (pintype "bidirectional"))
      (node (ref "IC2") (pin "31") (pinfunction "__IO_12_31") (pintype "bidirectional"))
    )
    (net (code "162") (name "/ZX_A14") (class "Default")
      (node (ref "IC10") (pin "17") (pinfunction "B2_17") (pintype "bidirectional"))
      (node (ref "IC2") (pin "30") (pinfunction "__IO_11_30") (pintype "bidirectional"))
    )
    (net (code "163") (name "/ZX_A15") (class "Default")
      (node (ref "IC10") (pin "18") (pinfunction "B1_18") (pintype "bidirectional"))
      (node (ref "IC2") (pin "28") (pinfunction "__IO_10_28") (pintype "bidirectional"))
    )
    (net (code "164") (name "GND") (class "Default")
      (node (ref "C1") (pin "1") (pinfunction "1_1") (pintype "passive"))
      (node (ref "C10") (pin "2") (pinfunction "2_2") (pintype "passive"))
      (node (ref "C11") (pin "2") (pinfunction "2_2") (pintype "passive"))
      (node (ref "C12") (pin "2") (pinfunction "2_2") (pintype "passive"))
      (node (ref "C13") (pin "2") (pinfunction "2_2") (pintype "passive"))
      (node (ref "C14") (pin "2") (pinfunction "2_2") (pintype "passive"))
      (node (ref "C15") (pin "2") (pinfunction "2_2") (pintype "passive"))
      (node (ref "C16") (pin "2") (pinfunction "2_2") (pintype "passive"))
      (node (ref "C17") (pin "2") (pinfunction "2_2") (pintype "passive"))
      (node (ref "C18") (pin "2") (pinfunction "2_2") (pintype "passive"))
      (node (ref "C19") (pin "2") (pinfunction "2_2") (pintype "passive"))
      (node (ref "C2") (pin "1") (pinfunction "1_1") (pintype "passive"))
      (node (ref "C20") (pin "2") (pinfunction "2_2") (pintype "passive"))
      (node (ref "C21") (pin "2") (pinfunction "2_2") (pintype "passive"))
      (node (ref "C22") (pin "2") (pinfunction "2_2") (pintype "passive"))
      (node (ref "C23") (pin "2") (pinfunction "2_2") (pintype "passive"))
      (node (ref "C24") (pin "2") (pinfunction "2_2") (pintype "passive"))
      (node (ref "C25") (pin "2") (pinfunction "2_2") (pintype "passive"))
      (node (ref "C26") (pin "2") (pinfunction "2_2") (pintype "passive"))
      (node (ref "C27") (pin "2") (pinfunction "2_2") (pintype "passive"))
      (node (ref "C28") (pin "2") (pinfunction "2_2") (pintype "passive"))
      (node (ref "C29") (pin "2") (pinfunction "2_2") (pintype "passive"))
      (node (ref "C3") (pin "2") (pinfunction "2_2") (pintype "passive"))
      (node (ref "C30") (pin "2") (pinfunction "2_2") (pintype "passive"))
      (node (ref "C31") (pin "1") (pinfunction "1_1") (pintype "passive"))
      (node (ref "C32") (pin "1") (pinfunction "1_1") (pintype "passive"))
      (node (ref "C33") (pin "1") (pinfunction "1_1") (pintype "passive"))
      (node (ref "C34") (pin "1") (pinfunction "1_1") (pintype "passive"))
      (node (ref "C35") (pin "1") (pinfunction "1_1") (pintype "passive"))
      (node (ref "C36") (pin "1") (pinfunction "1_1") (pintype "passive"))
      (node (ref "C37") (pin "2") (pinfunction "2_2") (pintype "passive"))
      (node (ref "C38") (pin "1") (pinfunction "1_1") (pintype "passive"))
      (node (ref "C39") (pin "1") (pinfunction "1_1") (pintype "passive"))
      (node (ref "C4") (pin "2") (pinfunction "2_2") (pintype "passive"))
      (node (ref "C40") (pin "1") (pinfunction "1_1") (pintype "passive"))
      (node (ref "C41") (pin "2") (pinfunction "2_2") (pintype "passive"))
      (node (ref "C45") (pin "1") (pinfunction "1_1") (pintype "passive"))
      (node (ref "C46") (pin "1") (pinfunction "1_1") (pintype "passive"))
      (node (ref "C47") (pin "1") (pinfunction "1_1") (pintype "passive"))
      (node (ref "C48") (pin "1") (pinfunction "1_1") (pintype "passive"))
      (node (ref "C49") (pin "1") (pinfunction "1_1") (pintype "passive"))
      (node (ref "C5") (pin "2") (pinfunction "2_2") (pintype "passive"))
      (node (ref "C50") (pin "2") (pinfunction "2_2") (pintype "passive"))
      (node (ref "C51") (pin "1") (pinfunction "1_1") (pintype "passive"))
      (node (ref "C52") (pin "2") (pinfunction "2_2") (pintype "passive"))
      (node (ref "C53") (pin "2") (pinfunction "2_2") (pintype "passive"))
      (node (ref "C56") (pin "2") (pinfunction "2_2") (pintype "passive"))
      (node (ref "C57") (pin "MINUS") (pinfunction "-_MINUS") (pintype "passive"))
      (node (ref "C58") (pin "1") (pinfunction "1_1") (pintype "passive"))
      (node (ref "C59") (pin "-") (pinfunction "-_-") (pintype "passive"))
      (node (ref "C6") (pin "2") (pinfunction "2_2") (pintype "passive"))
      (node (ref "C60") (pin "MINUS") (pinfunction "-_MINUS") (pintype "passive"))
      (node (ref "C7") (pin "2") (pinfunction "2_2") (pintype "passive"))
      (node (ref "C8") (pin "2") (pinfunction "2_2") (pintype "passive"))
      (node (ref "C9") (pin "2") (pinfunction "2_2") (pintype "passive"))
      (node (ref "CONN1") (pin "A14") (pinfunction "GND_A14") (pintype "power_in"))
      (node (ref "CONN1") (pin "A6") (pinfunction "GND_A6") (pintype "power_in"))
      (node (ref "CONN1") (pin "A7") (pinfunction "GND_A7") (pintype "power_in"))
      (node (ref "IC1") (pin "2") (pinfunction "GND_2") (pintype "power_in"))
      (node (ref "IC10") (pin "10") (pinfunction "GND_10") (pintype "power_in"))
      (node (ref "IC10") (pin "19") (pinfunction "G_19") (pintype "input"))
      (node (ref "IC11") (pin "10") (pinfunction "GND_10") (pintype "power_in"))
      (node (ref "IC11") (pin "19") (pinfunction "G_19") (pintype "input"))
      (node (ref "IC12") (pin "7") (pinfunction "GND_7") (pintype "power_in"))
      (node (ref "IC13") (pin "7") (pinfunction "GND_7") (pintype "power_in"))
      (node (ref "IC2") (pin "108") (pinfunction "__GNDA2_108") (pintype "power_in"))
      (node (ref "IC2") (pin "118") (pinfunction "__GND_12_118") (pintype "power_in"))
      (node (ref "IC2") (pin "123") (pinfunction "__GND_13_123") (pintype "power_in"))
      (node (ref "IC2") (pin "131") (pinfunction "__GND_14_131") (pintype "power_in"))
      (node (ref "IC2") (pin "140") (pinfunction "__GND_15_140") (pintype "power_in"))
      (node (ref "IC2") (pin "145") (pinfunction "TP_145") (pintype "bidirectional"))
      (node (ref "IC2") (pin "19") (pinfunction "__GND_2_19") (pintype "power_in"))
      (node (ref "IC2") (pin "21") (pinfunction "__NCE_21") (pintype "bidirectional"))
      (node (ref "IC2") (pin "22") (pinfunction "__GND_3_22") (pintype "power_in"))
      (node (ref "IC2") (pin "27") (pinfunction "__GND_4_27") (pintype "power_in"))
      (node (ref "IC2") (pin "36") (pinfunction "__GNDA1_36") (pintype "power_in"))
      (node (ref "IC2") (pin "4") (pinfunction "__GND_1_4") (pintype "power_in"))
      (node (ref "IC2") (pin "41") (pinfunction "__GND_5_41") (pintype "power_in"))
      (node (ref "IC2") (pin "48") (pinfunction "__GND_6_48") (pintype "power_in"))
      (node (ref "IC2") (pin "57") (pinfunction "__GND_7_57") (pintype "power_in"))
      (node (ref "IC2") (pin "63") (pinfunction "__GND_8_63") (pintype "power_in"))
      (node (ref "IC2") (pin "79") (pinfunction "__GND_9_79") (pintype "power_in"))
      (node (ref "IC2") (pin "82") (pinfunction "__GND_10_82") (pintype "power_in"))
      (node (ref "IC2") (pin "94") (pinfunction "__MSEL0_94") (pintype "bidirectional"))
      (node (ref "IC2") (pin "95") (pinfunction "__GND_11_95") (pintype "power_in"))
      (node (ref "IC2") (pin "96") (pinfunction "__MSEL1_96") (pintype "bidirectional"))
      (node (ref "IC3") (pin "10") (pinfunction "GND_10") (pintype "power_in"))
      (node (ref "IC3") (pin "19") (pinfunction "G_19") (pintype "input"))
      (node (ref "IC4") (pin "10") (pinfunction "GND_10") (pintype "power_in"))
      (node (ref "IC5") (pin "4") (pinfunction "GND_4") (pintype "power_in"))
      (node (ref "IC6") (pin "4") (pinfunction "GND_4") (pintype "power_in"))
      (node (ref "IC7") (pin "3") (pinfunction "GND_3") (pintype "power_in"))
      (node (ref "IC8") (pin "2") (pinfunction "GND_2") (pintype "power_in"))
      (node (ref "IC9") (pin "4") (pinfunction "GND_4") (pintype "power_in"))
      (node (ref "J1") (pin "10") (pinfunction "10_10") (pintype "passive"))
      (node (ref "J1") (pin "2") (pinfunction "2_2") (pintype "passive"))
      (node (ref "J2") (pin "6") (pinfunction "VSS_6") (pintype "power_in"))
      (node (ref "J2") (pin "9") (pinfunction "VSS_9") (pintype "power_in"))
      (node (ref "Q1") (pin "2") (pinfunction "S_2") (pintype "passive"))
      (node (ref "Q2") (pin "1") (pinfunction "S_1") (pintype "passive"))
      (node (ref "Q2") (pin "4") (pinfunction "S_4") (pintype "passive"))
      (node (ref "Q3") (pin "2") (pinfunction "S_2") (pintype "passive"))
      (node (ref "R10") (pin "2") (pinfunction "2_2") (pintype "passive"))
      (node (ref "R17") (pin "1") (pinfunction "1_1") (pintype "passive"))
      (node (ref "R18") (pin "1") (pinfunction "1_1") (pintype "passive"))
      (node (ref "R23") (pin "2") (pinfunction "2_2") (pintype "passive"))
      (node (ref "R26") (pin "1") (pinfunction "1_1") (pintype "passive"))
      (node (ref "R43") (pin "1") (pinfunction "1_1") (pintype "passive"))
      (node (ref "R45") (pin "2") (pinfunction "2_2") (pintype "passive"))
      (node (ref "R54") (pin "2") (pinfunction "2_2") (pintype "passive"))
      (node (ref "R55") (pin "2") (pinfunction "2_2") (pintype "passive"))
      (node (ref "R57") (pin "1") (pinfunction "1_1") (pintype "passive"))
      (node (ref "S1") (pin "A2") (pinfunction "1_A2") (pintype "passive"))
      (node (ref "S2") (pin "A2") (pinfunction "1_A2") (pintype "passive"))
      (node (ref "S3") (pin "A2") (pinfunction "1_A2") (pintype "passive"))
      (node (ref "TP4") (pin "TP") (pinfunction "TP_TP") (pintype "input"))
      (node (ref "TV26") (pin "1") (pinfunction "COM_1") (pintype "bidirectional"))
      (node (ref "U$1") (pin "2") (pinfunction "GND_2") (pintype "power_in"))
      (node (ref "U$3") (pin "2") (pinfunction "GND_2") (pintype "power_in"))
      (node (ref "U$5") (pin "A2") (pinfunction "GND_A2") (pintype "power_in"))
      (node (ref "U$5") (pin "B2") (pinfunction "GND_B2") (pintype "power_in"))
      (node (ref "U1") (pin "1") (pinfunction "GND_1") (pintype "bidirectional"))
      (node (ref "U1") (pin "15") (pinfunction "GND_15") (pintype "bidirectional"))
      (node (ref "U1") (pin "38") (pinfunction "GND_38") (pintype "bidirectional"))
      (node (ref "U1") (pin "GND") (pinfunction "GND_GND") (pintype "bidirectional"))
      (node (ref "USB2") (pin "GND") (pinfunction "GND_GND") (pintype "bidirectional"))
      (node (ref "USB3") (pin "P5") (pinfunction "GND_P5") (pintype "bidirectional"))
    )
    (net (code "165") (name "Net-(C42-Pad2)") (class "Default")
      (node (ref "C42") (pin "2") (pinfunction "2_2") (pintype "passive"))
      (node (ref "R13") (pin "1") (pinfunction "1_1") (pintype "passive"))
    )
    (net (code "166") (name "Net-(C43-Pad2)") (class "Default")
      (node (ref "C43") (pin "2") (pinfunction "2_2") (pintype "passive"))
      (node (ref "R14") (pin "1") (pinfunction "1_1") (pintype "passive"))
    )
    (net (code "167") (name "Net-(C44-Pad1)") (class "Default")
      (node (ref "C44") (pin "1") (pinfunction "1_1") (pintype "passive"))
      (node (ref "R16") (pin "2") (pinfunction "2_2") (pintype "passive"))
      (node (ref "R18") (pin "2") (pinfunction "2_2") (pintype "passive"))
      (node (ref "R20") (pin "1") (pinfunction "1_1") (pintype "passive"))
    )
    (net (code "168") (name "Net-(IC2-__CLK2)") (class "Default")
      (node (ref "IC2") (pin "24") (pinfunction "__CLK2_24") (pintype "input"))
      (node (ref "U$1") (pin "3") (pinfunction "FO_3") (pintype "output"))
    )
    (net (code "169") (name "Net-(IC3A-A1)") (class "Default")
      (node (ref "IC3") (pin "2") (pinfunction "A1_2") (pintype "bidirectional"))
      (node (ref "RN1") (pin "8") (pinfunction "2_8") (pintype "passive"))
    )
    (net (code "170") (name "Net-(IC3A-A2)") (class "Default")
      (node (ref "IC3") (pin "3") (pinfunction "A2_3") (pintype "bidirectional"))
      (node (ref "RN1") (pin "7") (pinfunction "2_7") (pintype "passive"))
    )
    (net (code "171") (name "Net-(IC3A-A3)") (class "Default")
      (node (ref "IC3") (pin "4") (pinfunction "A3_4") (pintype "bidirectional"))
      (node (ref "RN1") (pin "6") (pinfunction "2_6") (pintype "passive"))
    )
    (net (code "172") (name "Net-(IC3A-A4)") (class "Default")
      (node (ref "IC3") (pin "5") (pinfunction "A4_5") (pintype "bidirectional"))
      (node (ref "RN1") (pin "5") (pinfunction "2_5") (pintype "passive"))
    )
    (net (code "173") (name "Net-(IC3A-A5)") (class "Default")
      (node (ref "IC3") (pin "6") (pinfunction "A5_6") (pintype "bidirectional"))
      (node (ref "RN2") (pin "8") (pinfunction "2_8") (pintype "passive"))
    )
    (net (code "174") (name "Net-(IC3A-A6)") (class "Default")
      (node (ref "IC3") (pin "7") (pinfunction "A6_7") (pintype "bidirectional"))
      (node (ref "RN2") (pin "7") (pinfunction "2_7") (pintype "passive"))
    )
    (net (code "175") (name "Net-(IC3A-A7)") (class "Default")
      (node (ref "IC3") (pin "8") (pinfunction "A7_8") (pintype "bidirectional"))
      (node (ref "RN2") (pin "6") (pinfunction "2_6") (pintype "passive"))
    )
    (net (code "176") (name "Net-(IC3A-A8)") (class "Default")
      (node (ref "IC3") (pin "9") (pinfunction "A8_9") (pintype "bidirectional"))
      (node (ref "RN2") (pin "5") (pinfunction "2_5") (pintype "passive"))
    )
    (net (code "177") (name "Net-(IC4A-A1)") (class "Default")
      (node (ref "IC4") (pin "2") (pinfunction "A1_2") (pintype "bidirectional"))
      (node (ref "RN7") (pin "8") (pinfunction "2_8") (pintype "passive"))
    )
    (net (code "178") (name "Net-(IC4A-A2)") (class "Default")
      (node (ref "IC4") (pin "3") (pinfunction "A2_3") (pintype "bidirectional"))
      (node (ref "RN7") (pin "7") (pinfunction "2_7") (pintype "passive"))
    )
    (net (code "179") (name "Net-(IC4A-A3)") (class "Default")
      (node (ref "IC4") (pin "4") (pinfunction "A3_4") (pintype "bidirectional"))
      (node (ref "RN7") (pin "6") (pinfunction "2_6") (pintype "passive"))
    )
    (net (code "180") (name "Net-(IC4A-A4)") (class "Default")
      (node (ref "IC4") (pin "5") (pinfunction "A4_5") (pintype "bidirectional"))
      (node (ref "RN7") (pin "5") (pinfunction "2_5") (pintype "passive"))
    )
    (net (code "181") (name "Net-(IC4A-A5)") (class "Default")
      (node (ref "IC4") (pin "6") (pinfunction "A5_6") (pintype "bidirectional"))
      (node (ref "RN8") (pin "8") (pinfunction "2_8") (pintype "passive"))
    )
    (net (code "182") (name "Net-(IC4A-A6)") (class "Default")
      (node (ref "IC4") (pin "7") (pinfunction "A6_7") (pintype "bidirectional"))
      (node (ref "RN8") (pin "7") (pinfunction "2_7") (pintype "passive"))
    )
    (net (code "183") (name "Net-(IC4A-A7)") (class "Default")
      (node (ref "IC4") (pin "8") (pinfunction "A7_8") (pintype "bidirectional"))
      (node (ref "RN8") (pin "6") (pinfunction "2_6") (pintype "passive"))
    )
    (net (code "184") (name "Net-(IC4A-A8)") (class "Default")
      (node (ref "IC4") (pin "9") (pinfunction "A8_9") (pintype "bidirectional"))
      (node (ref "RN8") (pin "5") (pinfunction "2_5") (pintype "passive"))
    )
    (net (code "185") (name "Net-(IC5-BST)") (class "Default")
      (node (ref "IC5") (pin "5") (pinfunction "BST_5") (pintype "passive"))
      (node (ref "R13") (pin "2") (pinfunction "2_2") (pintype "passive"))
    )
    (net (code "186") (name "Net-(IC5-EN)") (class "Default")
      (node (ref "IC5") (pin "6") (pinfunction "EN_6") (pintype "input"))
      (node (ref "R11") (pin "1") (pinfunction "1_1") (pintype "passive"))
    )
    (net (code "187") (name "Net-(IC5-FB)") (class "Default")
      (node (ref "IC5") (pin "8") (pinfunction "FB_8") (pintype "passive"))
      (node (ref "R15") (pin "1") (pinfunction "1_1") (pintype "passive"))
    )
    (net (code "188") (name "Net-(IC5-SS)") (class "Default")
      (node (ref "C38") (pin "2") (pinfunction "2_2") (pintype "passive"))
      (node (ref "IC5") (pin "1") (pinfunction "SS_1") (pintype "passive"))
    )
    (net (code "189") (name "Net-(IC5-VCC)") (class "Default")
      (node (ref "C35") (pin "2") (pinfunction "2_2") (pintype "passive"))
      (node (ref "IC5") (pin "7") (pinfunction "VCC_7") (pintype "passive"))
    )
    (net (code "190") (name "Net-(IC6-BST)") (class "Default")
      (node (ref "IC6") (pin "5") (pinfunction "BST_5") (pintype "passive"))
      (node (ref "R14") (pin "2") (pinfunction "2_2") (pintype "passive"))
    )
    (net (code "191") (name "Net-(IC6-EN)") (class "Default")
      (node (ref "C58") (pin "2") (pinfunction "2_2") (pintype "passive"))
      (node (ref "IC6") (pin "6") (pinfunction "EN_6") (pintype "input"))
      (node (ref "R12") (pin "1") (pinfunction "1_1") (pintype "passive"))
    )
    (net (code "192") (name "Net-(IC6-FB)") (class "Default")
      (node (ref "IC6") (pin "8") (pinfunction "FB_8") (pintype "passive"))
      (node (ref "R16") (pin "1") (pinfunction "1_1") (pintype "passive"))
    )
    (net (code "193") (name "Net-(IC6-SS)") (class "Default")
      (node (ref "C39") (pin "2") (pinfunction "2_2") (pintype "passive"))
      (node (ref "IC6") (pin "1") (pinfunction "SS_1") (pintype "passive"))
    )
    (net (code "194") (name "Net-(IC6-VCC)") (class "Default")
      (node (ref "C36") (pin "2") (pinfunction "2_2") (pintype "passive"))
      (node (ref "IC6") (pin "7") (pinfunction "VCC_7") (pintype "passive"))
    )
    (net (code "195") (name "Net-(IC7-DM)") (class "Default")
      (node (ref "IC7") (pin "2") (pinfunction "DM_2") (pintype "passive"))
      (node (ref "USB3") (pin "P2") (pinfunction "D-_P2") (pintype "bidirectional"))
    )
    (net (code "196") (name "Net-(IC7-DP)") (class "Default")
      (node (ref "IC7") (pin "1") (pinfunction "DP_1") (pintype "passive"))
      (node (ref "USB3") (pin "P3") (pinfunction "D+_P3") (pintype "bidirectional"))
    )
    (net (code "197") (name "Net-(IC10A-A1)") (class "Default")
      (node (ref "IC10") (pin "2") (pinfunction "A1_2") (pintype "bidirectional"))
      (node (ref "RN3") (pin "8") (pinfunction "2_8") (pintype "passive"))
    )
    (net (code "198") (name "Net-(IC10A-A2)") (class "Default")
      (node (ref "IC10") (pin "3") (pinfunction "A2_3") (pintype "bidirectional"))
      (node (ref "RN3") (pin "7") (pinfunction "2_7") (pintype "passive"))
    )
    (net (code "199") (name "Net-(IC10A-A3)") (class "Default")
      (node (ref "IC10") (pin "4") (pinfunction "A3_4") (pintype "bidirectional"))
      (node (ref "RN3") (pin "6") (pinfunction "2_6") (pintype "passive"))
    )
    (net (code "200") (name "Net-(IC10A-A4)") (class "Default")
      (node (ref "IC10") (pin "5") (pinfunction "A4_5") (pintype "bidirectional"))
      (node (ref "RN3") (pin "5") (pinfunction "2_5") (pintype "passive"))
    )
    (net (code "201") (name "Net-(IC10A-A5)") (class "Default")
      (node (ref "IC10") (pin "6") (pinfunction "A5_6") (pintype "bidirectional"))
      (node (ref "RN4") (pin "8") (pinfunction "2_8") (pintype "passive"))
    )
    (net (code "202") (name "Net-(IC10A-A6)") (class "Default")
      (node (ref "IC10") (pin "7") (pinfunction "A6_7") (pintype "bidirectional"))
      (node (ref "RN4") (pin "7") (pinfunction "2_7") (pintype "passive"))
    )
    (net (code "203") (name "Net-(IC10A-A7)") (class "Default")
      (node (ref "IC10") (pin "8") (pinfunction "A7_8") (pintype "bidirectional"))
      (node (ref "RN4") (pin "6") (pinfunction "2_6") (pintype "passive"))
    )
    (net (code "204") (name "Net-(IC10A-A8)") (class "Default")
      (node (ref "IC10") (pin "9") (pinfunction "A8_9") (pintype "bidirectional"))
      (node (ref "RN4") (pin "5") (pinfunction "2_5") (pintype "passive"))
    )
    (net (code "205") (name "Net-(IC11A-A1)") (class "Default")
      (node (ref "IC11") (pin "2") (pinfunction "A1_2") (pintype "bidirectional"))
      (node (ref "RN5") (pin "8") (pinfunction "2_8") (pintype "passive"))
    )
    (net (code "206") (name "Net-(IC11A-A2)") (class "Default")
      (node (ref "IC11") (pin "3") (pinfunction "A2_3") (pintype "bidirectional"))
      (node (ref "RN5") (pin "7") (pinfunction "2_7") (pintype "passive"))
    )
    (net (code "207") (name "Net-(IC11A-A3)") (class "Default")
      (node (ref "IC11") (pin "4") (pinfunction "A3_4") (pintype "bidirectional"))
      (node (ref "RN5") (pin "6") (pinfunction "2_6") (pintype "passive"))
    )
    (net (code "208") (name "Net-(IC11A-A4)") (class "Default")
      (node (ref "IC11") (pin "5") (pinfunction "A4_5") (pintype "bidirectional"))
      (node (ref "RN5") (pin "5") (pinfunction "2_5") (pintype "passive"))
    )
    (net (code "209") (name "Net-(IC11A-A5)") (class "Default")
      (node (ref "IC11") (pin "6") (pinfunction "A5_6") (pintype "bidirectional"))
      (node (ref "RN6") (pin "8") (pinfunction "2_8") (pintype "passive"))
    )
    (net (code "210") (name "Net-(IC11A-A6)") (class "Default")
      (node (ref "IC11") (pin "7") (pinfunction "A6_7") (pintype "bidirectional"))
      (node (ref "RN6") (pin "7") (pinfunction "2_7") (pintype "passive"))
    )
    (net (code "211") (name "Net-(IC11A-A7)") (class "Default")
      (node (ref "IC11") (pin "8") (pinfunction "A7_8") (pintype "bidirectional"))
      (node (ref "RN6") (pin "6") (pinfunction "2_6") (pintype "passive"))
    )
    (net (code "212") (name "Net-(IC11A-A8)") (class "Default")
      (node (ref "IC11") (pin "9") (pinfunction "A8_9") (pintype "bidirectional"))
      (node (ref "RN6") (pin "5") (pinfunction "2_5") (pintype "passive"))
    )
    (net (code "213") (name "Net-(IC12-DM)") (class "Default")
      (node (ref "IC12") (pin "10") (pinfunction "DM_10") (pintype "bidirectional"))
      (node (ref "R36") (pin "1") (pinfunction "1_1") (pintype "passive"))
    )
    (net (code "214") (name "Net-(IC12-DP)") (class "Default")
      (node (ref "IC12") (pin "11") (pinfunction "DP_11") (pintype "bidirectional"))
      (node (ref "R35") (pin "1") (pinfunction "1_1") (pintype "passive"))
    )
    (net (code "215") (name "Net-(IC13C-O)") (class "Default")
      (node (ref "IC13") (pin "6") (pinfunction "O_6") (pintype "open_collector"))
      (node (ref "Q4") (pin "2") (pinfunction "G_2") (pintype "passive"))
      (node (ref "R25") (pin "2") (pinfunction "2_2") (pintype "passive"))
    )
    (net (code "216") (name "Net-(LED1-PadC)") (class "Default")
      (node (ref "LED1") (pin "C") (pinfunction "C_C") (pintype "passive"))
      (node (ref "R21") (pin "1") (pinfunction "1_1") (pintype "passive"))
    )
    (net (code "217") (name "Net-(LED2-PadC)") (class "Default")
      (node (ref "LED2") (pin "C") (pinfunction "C_C") (pintype "passive"))
      (node (ref "R22") (pin "1") (pinfunction "1_1") (pintype "passive"))
    )
    (net (code "218") (name "Net-(LED3-PadC)") (class "Default")
      (node (ref "LED3") (pin "C") (pinfunction "C_C") (pintype "passive"))
      (node (ref "R23") (pin "1") (pinfunction "1_1") (pintype "passive"))
    )
    (net (code "219") (name "Net-(LED4-PadC)") (class "Default")
      (node (ref "LED4") (pin "C") (pinfunction "C_C") (pintype "passive"))
      (node (ref "R39") (pin "1") (pinfunction "1_1") (pintype "passive"))
    )
    (net (code "220") (name "Net-(LED5-PadC)") (class "Default")
      (node (ref "LED5") (pin "C") (pinfunction "C_C") (pintype "passive"))
      (node (ref "R40") (pin "1") (pinfunction "1_1") (pintype "passive"))
    )
    (net (code "221") (name "Net-(LED6-PadC)") (class "Default")
      (node (ref "LED6") (pin "C") (pinfunction "C_C") (pintype "passive"))
      (node (ref "R41") (pin "1") (pinfunction "1_1") (pintype "passive"))
    )
    (net (code "222") (name "Net-(Q2A-D)") (class "Default")
      (node (ref "Q2") (pin "3") (pinfunction "D_3") (pintype "passive"))
      (node (ref "R48") (pin "1") (pinfunction "1_1") (pintype "passive"))
    )
    (net (code "223") (name "Net-(Q2A-G)") (class "Default")
      (node (ref "Q2") (pin "5") (pinfunction "G_5") (pintype "passive"))
      (node (ref "Q2") (pin "6") (pinfunction "D_6") (pintype "passive"))
      (node (ref "R50") (pin "1") (pinfunction "1_1") (pintype "passive"))
    )
    (net (code "224") (name "Net-(Q2B-G)") (class "Default")
      (node (ref "Q2") (pin "2") (pinfunction "G_2") (pintype "passive"))
      (node (ref "R49") (pin "1") (pinfunction "1_1") (pintype "passive"))
    )
    (net (code "225") (name "Net-(Q3-D)") (class "Default")
      (node (ref "Q3") (pin "3") (pinfunction "D_3") (pintype "passive"))
      (node (ref "R52") (pin "1") (pinfunction "1_1") (pintype "passive"))
    )
    (net (code "226") (name "Net-(Q3-G)") (class "Default")
      (node (ref "Q3") (pin "1") (pinfunction "G_1") (pintype "passive"))
      (node (ref "R53") (pin "1") (pinfunction "1_1") (pintype "passive"))
      (node (ref "R54") (pin "1") (pinfunction "1_1") (pintype "passive"))
    )
    (net (code "227") (name "Net-(Q6A-D)") (class "Default")
      (node (ref "Q6") (pin "3") (pinfunction "D_3") (pintype "passive"))
      (node (ref "R29") (pin "1") (pinfunction "1_1") (pintype "passive"))
    )
    (net (code "228") (name "Net-(Q6B-D)") (class "Default")
      (node (ref "Q6") (pin "6") (pinfunction "D_6") (pintype "passive"))
      (node (ref "R33") (pin "1") (pinfunction "1_1") (pintype "passive"))
    )
    (net (code "229") (name "Net-(R15-Pad2)") (class "Default")
      (node (ref "R15") (pin "2") (pinfunction "2_2") (pintype "passive"))
      (node (ref "R17") (pin "2") (pinfunction "2_2") (pintype "passive"))
      (node (ref "R19") (pin "1") (pinfunction "1_1") (pintype "passive"))
    )
    (net (code "230") (name "Net-(R26-Pad2)") (class "Default")
      (node (ref "R26") (pin "2") (pinfunction "2_2") (pintype "passive"))
      (node (ref "R44") (pin "1") (pinfunction "1_1") (pintype "passive"))
      (node (ref "R46") (pin "2") (pinfunction "2_2") (pintype "passive"))
    )
    (net (code "231") (name "Net-(T2A-G)") (class "Default")
      (node (ref "R47") (pin "1") (pinfunction "1_1") (pintype "passive"))
      (node (ref "R48") (pin "2") (pinfunction "2_2") (pintype "passive"))
      (node (ref "T2") (pin "1") (pinfunction "G_1") (pintype "passive"))
    )
    (net (code "232") (name "Net-(T2B-G)") (class "Default")
      (node (ref "C54") (pin "1") (pinfunction "1_1") (pintype "passive"))
      (node (ref "R51") (pin "1") (pinfunction "1_1") (pintype "passive"))
      (node (ref "R52") (pin "2") (pinfunction "2_2") (pintype "passive"))
      (node (ref "T2") (pin "3") (pinfunction "G_3") (pintype "passive"))
    )
    (net (code "233") (name "PE") (class "Default")
      (node (ref "C50") (pin "1") (pinfunction "1_1") (pintype "passive"))
      (node (ref "J2") (pin "P1") (pinfunction "SHIELD_P1") (pintype "passive"))
      (node (ref "J2") (pin "P2") (pinfunction "SHIELD_P2") (pintype "passive"))
      (node (ref "J2") (pin "P3") (pinfunction "SHIELD_P3") (pintype "passive"))
      (node (ref "J2") (pin "P4") (pinfunction "SHIELD_P4") (pintype "passive"))
      (node (ref "R45") (pin "1") (pinfunction "1_1") (pintype "passive"))
      (node (ref "USB2") (pin "P$5") (pinfunction "SHIELD_P$5") (pintype "passive"))
      (node (ref "USB2") (pin "P$6") (pinfunction "SHIELD_P$6") (pintype "passive"))
      (node (ref "USB3") (pin "S1") (pinfunction "SHIELD_S1") (pintype "passive"))
      (node (ref "USB3") (pin "S2") (pinfunction "SHIELD_S2") (pintype "passive"))
      (node (ref "USB3") (pin "S3") (pinfunction "SHIELD_S3") (pintype "passive"))
      (node (ref "USB3") (pin "S4") (pinfunction "SHIELD_S4") (pintype "passive"))
      (node (ref "USB3") (pin "S5") (pinfunction "SHIELD_S5") (pintype "passive"))
      (node (ref "USB3") (pin "S6") (pinfunction "SHIELD_S6") (pintype "passive"))
    )
    (net (code "234") (name "unconnected-(CONN1-BUSACK-PadA26)") (class "Default")
      (node (ref "CONN1") (pin "A26") (pinfunction "BUSACK_A26") (pintype "bidirectional"))
    )
    (net (code "235") (name "unconnected-(CONN1-BUSREQ-PadA19)") (class "Default")
      (node (ref "CONN1") (pin "A19") (pinfunction "BUSREQ_A19") (pintype "bidirectional"))
    )
    (net (code "236") (name "unconnected-(CONN1-HALT-PadB15)") (class "Default")
      (node (ref "CONN1") (pin "B15") (pinfunction "HALT_B15") (pintype "bidirectional"))
    )
    (net (code "237") (name "unconnected-(CONN1-NC-PadB28)") (class "Default")
      (node (ref "CONN1") (pin "B28") (pinfunction "NC_B28") (pintype "bidirectional"))
    )
    (net (code "238") (name "unconnected-(CONN1-U-PadA18)") (class "Default")
      (node (ref "CONN1") (pin "A18") (pinfunction "U_A18") (pintype "bidirectional"))
    )
    (net (code "239") (name "unconnected-(CONN1-V-PadA17)") (class "Default")
      (node (ref "CONN1") (pin "A17") (pinfunction "V_A17") (pintype "bidirectional"))
    )
    (net (code "240") (name "unconnected-(CONN1-YL-PadA16)") (class "Default")
      (node (ref "CONN1") (pin "A16") (pinfunction "YL_A16") (pintype "bidirectional"))
    )
    (net (code "241") (name "unconnected-(IC2-__CLK3-Pad25)") (class "Default")
      (node (ref "IC2") (pin "25") (pinfunction "__CLK3_25") (pintype "input"))
    )
    (net (code "242") (name "unconnected-(IC2-__CLK4-Pad91)") (class "Default")
      (node (ref "IC2") (pin "91") (pinfunction "__CLK4_91") (pintype "input"))
    )
    (net (code "243") (name "unconnected-(IC2-__CLK5-Pad90)") (class "Default")
      (node (ref "IC2") (pin "90") (pinfunction "__CLK5_90") (pintype "input"))
    )
    (net (code "244") (name "unconnected-(IC2-__CLK6-Pad89)") (class "Default")
      (node (ref "IC2") (pin "89") (pinfunction "__CLK6_89") (pintype "input"))
    )
    (net (code "245") (name "unconnected-(IC2-__CLK7-Pad88)") (class "Default")
      (node (ref "IC2") (pin "88") (pinfunction "__CLK7_88") (pintype "input"))
    )
    (net (code "246") (name "unconnected-(J1-Pad6)") (class "Default")
      (node (ref "J1") (pin "6") (pinfunction "6_6") (pintype "passive"))
    )
    (net (code "247") (name "unconnected-(J1-Pad7)") (class "Default")
      (node (ref "J1") (pin "7") (pinfunction "7_7") (pintype "passive"))
    )
    (net (code "248") (name "unconnected-(J1-Pad8)") (class "Default")
      (node (ref "J1") (pin "8") (pinfunction "8_8") (pintype "passive"))
    )
    (net (code "249") (name "unconnected-(J2-DETECT_SWITCH-Pad10)") (class "Default")
      (node (ref "J2") (pin "10") (pinfunction "DETECT_SWITCH_10") (pintype "passive"))
    )
    (net (code "250") (name "unconnected-(U1-CLK-Pad20)") (class "Default")
      (node (ref "U1") (pin "20") (pinfunction "CLK_20") (pintype "bidirectional"))
    )
    (net (code "251") (name "unconnected-(U1-CMD-Pad19)") (class "Default")
      (node (ref "U1") (pin "19") (pinfunction "CMD_19") (pintype "bidirectional"))
    )
    (net (code "252") (name "unconnected-(U1-NC-Pad32)") (class "Default")
      (node (ref "U1") (pin "32") (pinfunction "NC_32") (pintype "bidirectional"))
    )
    (net (code "253") (name "unconnected-(U1-SD1-Pad22)") (class "Default")
      (node (ref "U1") (pin "22") (pinfunction "SD1_22") (pintype "bidirectional"))
    )
    (net (code "254") (name "unconnected-(U1-SD2-Pad17)") (class "Default")
      (node (ref "U1") (pin "17") (pinfunction "SD2_17") (pintype "bidirectional"))
    )
    (net (code "255") (name "unconnected-(U1-SD3-Pad18)") (class "Default")
      (node (ref "U1") (pin "18") (pinfunction "SD3_18") (pintype "bidirectional"))
    )
    (net (code "256") (name "unconnected-(U1-SDO-Pad21)") (class "Default")
      (node (ref "U1") (pin "21") (pinfunction "SDO_21") (pintype "bidirectional"))
    )
    (net (code "257") (name "unconnected-(U1-SENSOR_VN-Pad5)") (class "Default")
      (node (ref "U1") (pin "5") (pinfunction "SENSOR_VN_5") (pintype "input"))
    )
    (net (code "258") (name "unconnected-(USB3-USBID-PadP4)") (class "Default")
      (node (ref "USB3") (pin "P4") (pinfunction "USBID_P4") (pintype "bidirectional"))
    )
    (net (code "259") (name "unconnected-(USB3-VUSB-PadP1)") (class "Default")
      (node (ref "USB3") (pin "P1") (pinfunction "VUSB_P1") (pintype "bidirectional"))
    )
  )
)
